# 1_MCU.net
KiCad netlist of a schematic drawn in Altium Designer
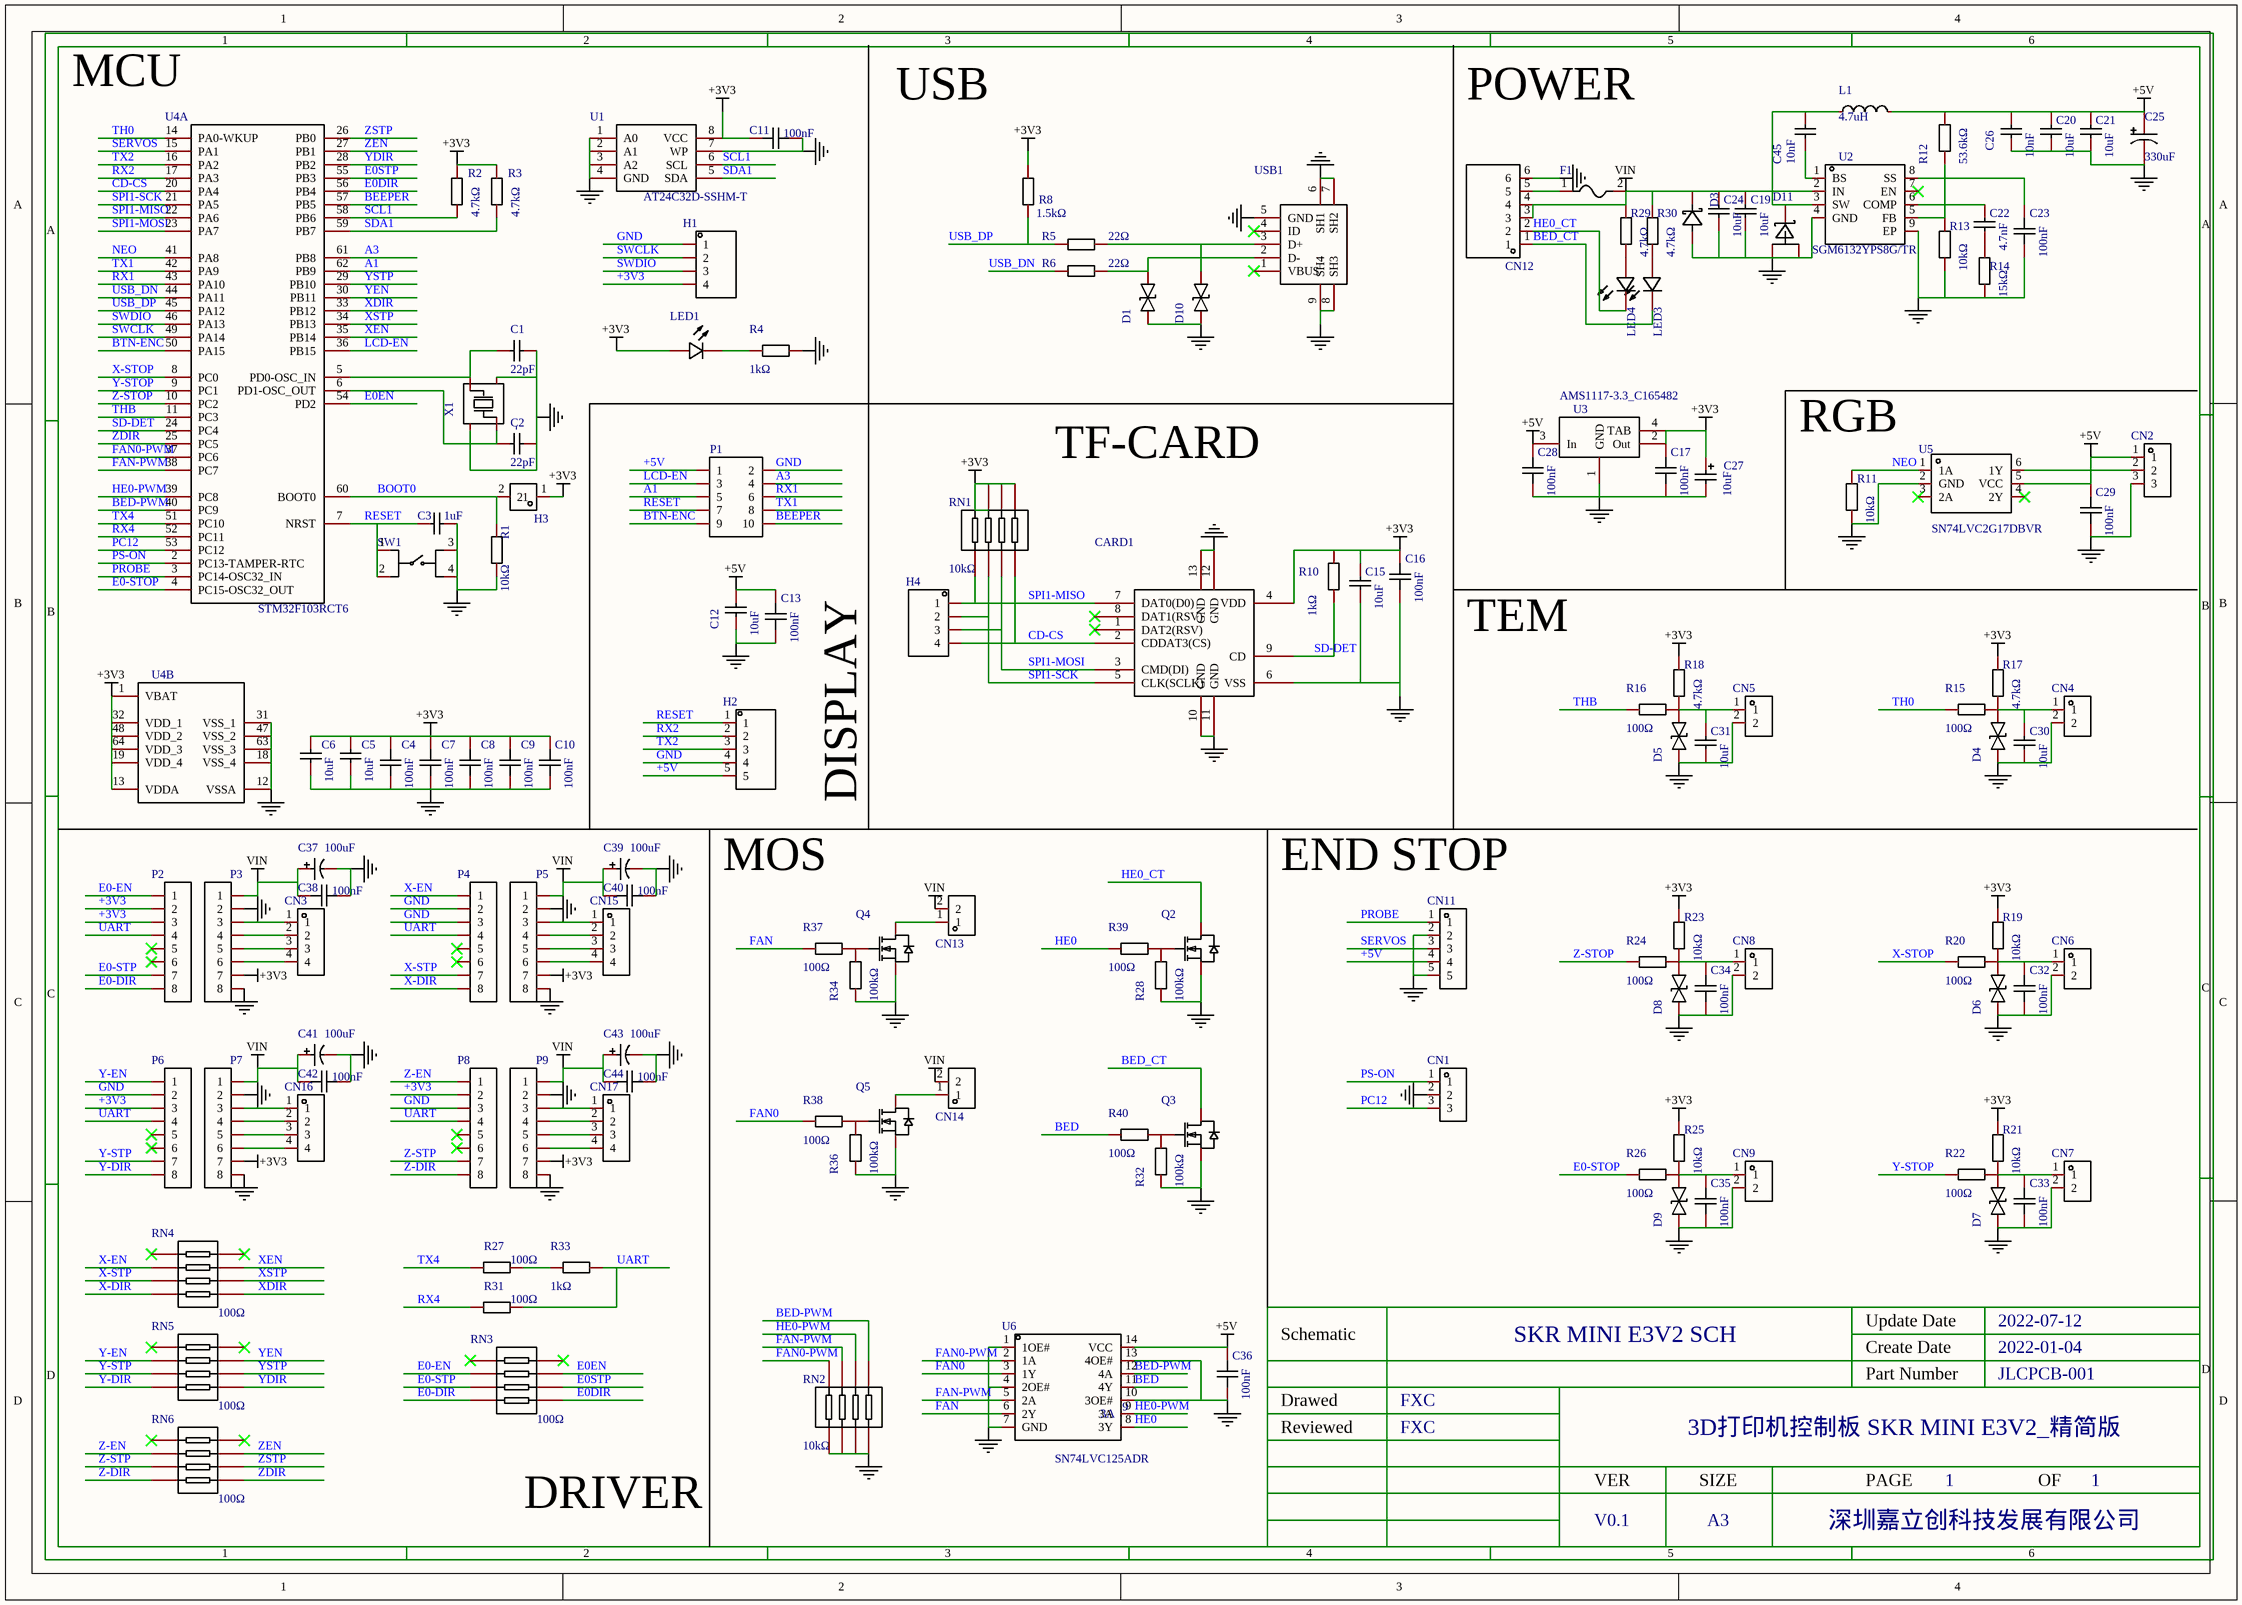
[diagram p0: 1_MCU.schdoc]

(export (version "E")
  (design (tool "Eeschema 10.0.6"))
  (components
    (comp (ref "C1")
      (value "22pF")
      (description "温度系数:NP0;电容体长:-;电容体宽:-;电容体厚度:-;精度:±5%;额定电压:50V;容值:22pF;")
      (fields
        (field (name "MANUFACTURER") "YAGEO(国巨)")
        (field (name "MANUFACTURER PART") "CC0603JRNPO9BN220")
      )
      (libsource (lib "altium-import") (part "root_0_CC0603JRNPO9BN220_"))
    )
    (comp (ref "C2")
      (value "22pF")
      (description "温度系数:NP0;电容体长:-;电容体宽:-;电容体厚度:-;精度:±5%;额定电压:50V;容值:22pF;")
      (fields
        (field (name "MANUFACTURER") "YAGEO(国巨)")
        (field (name "MANUFACTURER PART") "CC0603JRNPO9BN220")
      )
      (libsource (lib "altium-import") (part "root_0_CC0603JRNPO9BN220_"))
    )
    (comp (ref "C3")
      (value "1uF")
      (description "温度系数:X5R;额定电压:25V;电容体长:-;精度:±10%;电容体宽:-;电容体厚度:-;容值:1uF;")
      (fields
        (field (name "MANUFACTURER") "YAGEO(国巨)")
        (field (name "MANUFACTURER PART") "CC0603KRX5R8BB105")
      )
      (libsource (lib "altium-import") (part "root_0_CC0603KRX5R8BB105_"))
    )
    (comp (ref "C4")
      (value "100nF")
      (description "温度系数:X7R;容值:100nF;电容体长:-;精度:±10%;电容体宽:-;电容体厚度:-;额定电压:50V;")
      (fields
        (field (name "MANUFACTURER") "YAGEO(国巨)")
        (field (name "MANUFACTURER PART") "CC0603KRX7R9BB104")
      )
      (libsource (lib "altium-import") (part "root_1_CC0603KRX7R9BB104_"))
    )
    (comp (ref "C5")
      (value "10uF")
      (description "温度系数:X5R;精度:±10%;额定电压:16V;容值:10uF;")
      (fields (field (name "MANUFACTURER") "FH(风华)") (field (name "MANUFACTURER PART") "0603X106K160NT"))
      (libsource (lib "altium-import") (part "root_1_0603X106K160NT_"))
    )
    (comp (ref "C6")
      (value "10uF")
      (description "温度系数:X5R;精度:±10%;额定电压:16V;容值:10uF;")
      (fields (field (name "MANUFACTURER") "FH(风华)") (field (name "MANUFACTURER PART") "0603X106K160NT"))
      (libsource (lib "altium-import") (part "root_1_0603X106K160NT_"))
    )
    (comp (ref "C7")
      (value "100nF")
      (description "温度系数:X7R;容值:100nF;电容体长:-;精度:±10%;电容体宽:-;电容体厚度:-;额定电压:50V;")
      (fields
        (field (name "MANUFACTURER") "YAGEO(国巨)")
        (field (name "MANUFACTURER PART") "CC0603KRX7R9BB104")
      )
      (libsource (lib "altium-import") (part "root_1_CC0603KRX7R9BB104_"))
    )
    (comp (ref "C8")
      (value "100nF")
      (description "温度系数:X7R;容值:100nF;电容体长:-;精度:±10%;电容体宽:-;电容体厚度:-;额定电压:50V;")
      (fields
        (field (name "MANUFACTURER") "YAGEO(国巨)")
        (field (name "MANUFACTURER PART") "CC0603KRX7R9BB104")
      )
      (libsource (lib "altium-import") (part "root_1_CC0603KRX7R9BB104_"))
    )
    (comp (ref "C9")
      (value "100nF")
      (description "温度系数:X7R;容值:100nF;电容体长:-;精度:±10%;电容体宽:-;电容体厚度:-;额定电压:50V;")
      (fields
        (field (name "MANUFACTURER") "YAGEO(国巨)")
        (field (name "MANUFACTURER PART") "CC0603KRX7R9BB104")
      )
      (libsource (lib "altium-import") (part "root_1_CC0603KRX7R9BB104_"))
    )
    (comp (ref "C10")
      (value "100nF")
      (description "温度系数:X7R;容值:100nF;电容体长:-;精度:±10%;电容体宽:-;电容体厚度:-;额定电压:50V;")
      (fields
        (field (name "MANUFACTURER") "YAGEO(国巨)")
        (field (name "MANUFACTURER PART") "CC0603KRX7R9BB104")
      )
      (libsource (lib "altium-import") (part "root_1_CC0603KRX7R9BB104_"))
    )
    (comp (ref "C11")
      (value "100nF")
      (description "温度系数:X7R;容值:100nF;电容体长:-;精度:±10%;电容体宽:-;电容体厚度:-;额定电压:50V;")
      (fields
        (field (name "MANUFACTURER") "YAGEO(国巨)")
        (field (name "MANUFACTURER PART") "CC0603KRX7R9BB104")
      )
      (libsource (lib "altium-import") (part "root_2_CC0603KRX7R9BB104_"))
    )
    (comp (ref "C12")
      (value "10uF")
      (description "温度系数:X5R;精度:±10%;额定电压:16V;容值:10uF;")
      (fields (field (name "MANUFACTURER") "FH(风华)") (field (name "MANUFACTURER PART") "0603X106K160NT"))
      (libsource (lib "altium-import") (part "root_1_0603X106K160NT_"))
    )
    (comp (ref "C13")
      (value "100nF")
      (description "温度系数:X7R;容值:100nF;电容体长:-;精度:±10%;电容体宽:-;电容体厚度:-;额定电压:50V;")
      (fields
        (field (name "MANUFACTURER") "YAGEO(国巨)")
        (field (name "MANUFACTURER PART") "CC0603KRX7R9BB104")
      )
      (libsource (lib "altium-import") (part "root_1_CC0603KRX7R9BB104_"))
    )
    (comp (ref "C15")
      (value "10uF")
      (description "温度系数:X5R;精度:±10%;额定电压:16V;容值:10uF;")
      (fields (field (name "MANUFACTURER") "FH(风华)") (field (name "MANUFACTURER PART") "0603X106K160NT"))
      (libsource (lib "altium-import") (part "root_1_0603X106K160NT_"))
    )
    (comp (ref "C16")
      (value "100nF")
      (description "温度系数:X7R;容值:100nF;电容体长:-;精度:±10%;电容体宽:-;电容体厚度:-;额定电压:50V;")
      (fields
        (field (name "MANUFACTURER") "YAGEO(国巨)")
        (field (name "MANUFACTURER PART") "CC0603KRX7R9BB104")
      )
      (libsource (lib "altium-import") (part "root_1_CC0603KRX7R9BB104_"))
    )
    (comp (ref "C17")
      (value "100nF")
      (description "温度系数:X7R;容值:100nF;电容体长:-;精度:±10%;电容体宽:-;电容体厚度:-;额定电压:50V;")
      (fields
        (field (name "MANUFACTURER") "YAGEO(国巨)")
        (field (name "MANUFACTURER PART") "CC0603KRX7R9BB104")
      )
      (libsource (lib "altium-import") (part "root_1_CC0603KRX7R9BB104_"))
    )
    (comp (ref "C19")
      (value "10uF")
      (description "温度系数:X7R;精度:±10%;额定电压:50V;容值:10uF;")
      (fields
        (field (name "MANUFACTURER") "muRata(村田)")
        (field (name "MANUFACTURER PART") "GRM32ER71H106KA12L")
      )
      (libsource (lib "altium-import") (part "root_1_GRM32ER71H106KA12L_"))
    )
    (comp (ref "C20")
      (value "10uF")
      (description "温度系数:X7R;精度:±10%;额定电压:50V;容值:10uF;")
      (fields
        (field (name "MANUFACTURER") "muRata(村田)")
        (field (name "MANUFACTURER PART") "GRM32ER71H106KA12L")
      )
      (libsource (lib "altium-import") (part "root_1_GRM32ER71H106KA12L_"))
    )
    (comp (ref "C21")
      (value "10uF")
      (description "温度系数:X7R;精度:±10%;额定电压:50V;容值:10uF;")
      (fields
        (field (name "MANUFACTURER") "muRata(村田)")
        (field (name "MANUFACTURER PART") "GRM32ER71H106KA12L")
      )
      (libsource (lib "altium-import") (part "root_1_GRM32ER71H106KA12L_"))
    )
    (comp (ref "C22")
      (value "4.7nF")
      (description "温度系数:X7R;电容体长:-;精度:±10%;电容体宽:-;容值:4.7nF;电容体厚度:-;额定电压:50V;")
      (fields
        (field (name "MANUFACTURER") "YAGEO(国巨)")
        (field (name "MANUFACTURER PART") "CC0603KRX7R9BB472")
      )
      (libsource (lib "altium-import") (part "root_1_CC0603KRX7R9BB472_"))
    )
    (comp (ref "C23")
      (value "100nF")
      (description "温度系数:X7R;容值:100nF;电容体长:-;精度:±10%;电容体宽:-;电容体厚度:-;额定电压:50V;")
      (fields
        (field (name "MANUFACTURER") "YAGEO(国巨)")
        (field (name "MANUFACTURER PART") "CC0603KRX7R9BB104")
      )
      (libsource (lib "altium-import") (part "root_1_CC0603KRX7R9BB104_"))
    )
    (comp (ref "C24")
      (value "10uF")
      (description "温度系数:X7R;精度:±10%;额定电压:50V;容值:10uF;")
      (fields
        (field (name "MANUFACTURER") "muRata(村田)")
        (field (name "MANUFACTURER PART") "GRM32ER71H106KA12L")
      )
      (libsource (lib "altium-import") (part "root_1_GRM32ER71H106KA12L_"))
    )
    (comp (ref "C25")
      (value "330uF")
      (description "等效串联电阻:-;工作温度:-45℃~+105℃;纹波电流:-;工作寿命:2000hrs105℃;容值:330uF;电容体直径:8mm;精度:±20%;额定电压:25V;电容体长度:10mm;")
      (fields
        (field (name "MANUFACTURER") "lelon(台湾立隆)")
        (field (name "MANUFACTURER PART") "VEJ331M1ETR-0810")
      )
      (libsource (lib "altium-import") (part "root_0_VEJ331M1ETR-0810_"))
    )
    (comp (ref "C26")
      (value "10nF")
      (description "温度系数:X7R;电容体长:-;精度:±10%;电容体宽:-;电容体厚度:-;额定电压:50V;容值:10nF;")
      (fields
        (field (name "MANUFACTURER") "YAGEO(国巨)")
        (field (name "MANUFACTURER PART") "CC0603KRX7R9BB103")
      )
      (libsource (lib "altium-import") (part "root_1_CC0603KRX7R9BB103_"))
    )
    (comp (ref "C27")
      (value "10uF")
      (description "等效串联电阻:2.8Ω100kHz;工作温度:-55℃~+125℃;额定电压:16V;容值:10uF;精度:±10%;")
      (fields (field (name "MANUFACTURER") "AVX") (field (name "MANUFACTURER PART") "TAJB106K016RNJ"))
      (libsource (lib "altium-import") (part "root_3_TAJB106K016RNJ_"))
    )
    (comp (ref "C28")
      (value "100nF")
      (description "温度系数:X7R;容值:100nF;电容体长:-;精度:±10%;电容体宽:-;电容体厚度:-;额定电压:50V;")
      (fields
        (field (name "MANUFACTURER") "YAGEO(国巨)")
        (field (name "MANUFACTURER PART") "CC0603KRX7R9BB104")
      )
      (libsource (lib "altium-import") (part "root_1_CC0603KRX7R9BB104_"))
    )
    (comp (ref "C29")
      (value "100nF")
      (description "温度系数:X7R;容值:100nF;电容体长:-;精度:±10%;电容体宽:-;电容体厚度:-;额定电压:50V;")
      (fields
        (field (name "MANUFACTURER") "YAGEO(国巨)")
        (field (name "MANUFACTURER PART") "CC0603KRX7R9BB104")
      )
      (libsource (lib "altium-import") (part "root_1_CC0603KRX7R9BB104_"))
    )
    (comp (ref "C30")
      (value "10uF")
      (description "温度系数:X5R;精度:±10%;额定电压:16V;容值:10uF;")
      (fields (field (name "MANUFACTURER") "FH(风华)") (field (name "MANUFACTURER PART") "0603X106K160NT"))
      (libsource (lib "altium-import") (part "root_1_0603X106K160NT_"))
    )
    (comp (ref "C31")
      (value "10uF")
      (description "温度系数:X5R;精度:±10%;额定电压:16V;容值:10uF;")
      (fields (field (name "MANUFACTURER") "FH(风华)") (field (name "MANUFACTURER PART") "0603X106K160NT"))
      (libsource (lib "altium-import") (part "root_1_0603X106K160NT_"))
    )
    (comp (ref "C32")
      (value "100nF")
      (description "温度系数:X7R;容值:100nF;电容体长:-;精度:±10%;电容体宽:-;电容体厚度:-;额定电压:50V;")
      (fields
        (field (name "MANUFACTURER") "YAGEO(国巨)")
        (field (name "MANUFACTURER PART") "CC0603KRX7R9BB104")
      )
      (libsource (lib "altium-import") (part "root_1_CC0603KRX7R9BB104_"))
    )
    (comp (ref "C33")
      (value "100nF")
      (description "温度系数:X7R;容值:100nF;电容体长:-;精度:±10%;电容体宽:-;电容体厚度:-;额定电压:50V;")
      (fields
        (field (name "MANUFACTURER") "YAGEO(国巨)")
        (field (name "MANUFACTURER PART") "CC0603KRX7R9BB104")
      )
      (libsource (lib "altium-import") (part "root_1_CC0603KRX7R9BB104_"))
    )
    (comp (ref "C34")
      (value "100nF")
      (description "温度系数:X7R;容值:100nF;电容体长:-;精度:±10%;电容体宽:-;电容体厚度:-;额定电压:50V;")
      (fields
        (field (name "MANUFACTURER") "YAGEO(国巨)")
        (field (name "MANUFACTURER PART") "CC0603KRX7R9BB104")
      )
      (libsource (lib "altium-import") (part "root_1_CC0603KRX7R9BB104_"))
    )
    (comp (ref "C35")
      (value "100nF")
      (description "温度系数:X7R;容值:100nF;电容体长:-;精度:±10%;电容体宽:-;电容体厚度:-;额定电压:50V;")
      (fields
        (field (name "MANUFACTURER") "YAGEO(国巨)")
        (field (name "MANUFACTURER PART") "CC0603KRX7R9BB104")
      )
      (libsource (lib "altium-import") (part "root_1_CC0603KRX7R9BB104_"))
    )
    (comp (ref "C36")
      (value "100nF")
      (description "温度系数:X7R;容值:100nF;电容体长:-;精度:±10%;电容体宽:-;电容体厚度:-;额定电压:50V;")
      (fields
        (field (name "MANUFACTURER") "YAGEO(国巨)")
        (field (name "MANUFACTURER PART") "CC0603KRX7R9BB104")
      )
      (libsource (lib "altium-import") (part "root_1_CC0603KRX7R9BB104_"))
    )
    (comp (ref "C37")
      (value "100uF")
      (fields
        (field (name "MANUFACTURER") "CapXon(台湾丰宾)")
        (field (name "MANUFACTURER PART") "DV101M035E077ETR")
        (field (name "TOLERANCE") "±20%")
      )
      (libsource (lib "altium-import") (part "root_0_DV101M035E077ETR_"))
    )
    (comp (ref "C38")
      (value "100nF")
      (description "温度系数:X7R;容值:100nF;电容体长:-;精度:±10%;电容体宽:-;电容体厚度:-;额定电压:50V;")
      (fields
        (field (name "MANUFACTURER") "YAGEO(国巨)")
        (field (name "MANUFACTURER PART") "CC0603KRX7R9BB104")
      )
      (libsource (lib "altium-import") (part "root_2_CC0603KRX7R9BB104_"))
    )
    (comp (ref "C39")
      (value "100uF")
      (fields
        (field (name "MANUFACTURER") "CapXon(台湾丰宾)")
        (field (name "MANUFACTURER PART") "DV101M035E077ETR")
        (field (name "TOLERANCE") "±20%")
      )
      (libsource (lib "altium-import") (part "root_0_DV101M035E077ETR_"))
    )
    (comp (ref "C40")
      (value "100nF")
      (description "温度系数:X7R;容值:100nF;电容体长:-;精度:±10%;电容体宽:-;电容体厚度:-;额定电压:50V;")
      (fields
        (field (name "MANUFACTURER") "YAGEO(国巨)")
        (field (name "MANUFACTURER PART") "CC0603KRX7R9BB104")
      )
      (libsource (lib "altium-import") (part "root_2_CC0603KRX7R9BB104_"))
    )
    (comp (ref "C41")
      (value "100uF")
      (fields
        (field (name "MANUFACTURER") "CapXon(台湾丰宾)")
        (field (name "MANUFACTURER PART") "DV101M035E077ETR")
        (field (name "TOLERANCE") "±20%")
      )
      (libsource (lib "altium-import") (part "root_0_DV101M035E077ETR_"))
    )
    (comp (ref "C42")
      (value "100nF")
      (description "温度系数:X7R;容值:100nF;电容体长:-;精度:±10%;电容体宽:-;电容体厚度:-;额定电压:50V;")
      (fields
        (field (name "MANUFACTURER") "YAGEO(国巨)")
        (field (name "MANUFACTURER PART") "CC0603KRX7R9BB104")
      )
      (libsource (lib "altium-import") (part "root_2_CC0603KRX7R9BB104_"))
    )
    (comp (ref "C43")
      (value "100uF")
      (fields
        (field (name "MANUFACTURER") "CapXon(台湾丰宾)")
        (field (name "MANUFACTURER PART") "DV101M035E077ETR")
        (field (name "TOLERANCE") "±20%")
      )
      (libsource (lib "altium-import") (part "root_0_DV101M035E077ETR_"))
    )
    (comp (ref "C44")
      (value "100nF")
      (description "温度系数:X7R;容值:100nF;电容体长:-;精度:±10%;电容体宽:-;电容体厚度:-;额定电压:50V;")
      (fields
        (field (name "MANUFACTURER") "YAGEO(国巨)")
        (field (name "MANUFACTURER PART") "CC0603KRX7R9BB104")
      )
      (libsource (lib "altium-import") (part "root_2_CC0603KRX7R9BB104_"))
    )
    (comp (ref "C45")
      (value "10nF")
      (description "温度系数:X7R;电容体长:-;精度:±10%;电容体宽:-;电容体厚度:-;额定电压:50V;容值:10nF;")
      (fields
        (field (name "MANUFACTURER") "YAGEO(国巨)")
        (field (name "MANUFACTURER PART") "CC0603KRX7R9BB103")
      )
      (libsource (lib "altium-import") (part "root_1_CC0603KRX7R9BB103_"))
    )
    (comp (ref "CARD1")
      (value "TF-01A")
      (description "工作温度范围:-;本体最大高度:-;触头镀层:-;连接器类型:卡座;卡类型:MicroSD卡(TF卡);焊接温度(最大值):-;触头材质:-;卡连接方式:自弹式;")
      (fields (field (name "MANUFACTURER") "韩国韩荣"))
      (libsource (lib "altium-import") (part "root_0_TF-01A_"))
    )
    (comp (ref "CN1")
      (value "HX25003-3A")
      (description "系列:-;连接器类型:-;触头类型:-;间距:-;针脚数:-;")
      (fields (field (name "MANUFACTURER") "HX(红星)"))
      (libsource (lib "altium-import") (part "root_0_HX25003-3A_"))
    )
    (comp (ref "CN2")
      (value "HX25003-3A")
      (description "系列:-;连接器类型:-;触头类型:-;间距:-;针脚数:-;")
      (fields (field (name "MANUFACTURER") "HX(红星)"))
      (libsource (lib "altium-import") (part "root_0_HX25003-3A_"))
    )
    (comp (ref "CN3")
      (value "HX25003-4A")
      (description "系列:-;连接器类型:-;触头类型:-;间距:-;针脚数:-;")
      (fields (field (name "MANUFACTURER") "HX(红星)"))
      (libsource (lib "altium-import") (part "root_0_HX25003-4A_"))
    )
    (comp (ref "CN4")
      (value "HX25003-2A")
      (description "系列:-;连接器类型:-;触头类型:-;间距:-;针脚数:-;")
      (fields (field (name "MANUFACTURER") "HX(红星)"))
      (libsource (lib "altium-import") (part "root_0_HX25003-2A_"))
    )
    (comp (ref "CN5")
      (value "HX25003-2A")
      (description "系列:-;连接器类型:-;触头类型:-;间距:-;针脚数:-;")
      (fields (field (name "MANUFACTURER") "HX(红星)"))
      (libsource (lib "altium-import") (part "root_0_HX25003-2A_"))
    )
    (comp (ref "CN6")
      (value "HX25003-2A")
      (description "系列:-;连接器类型:-;触头类型:-;间距:-;针脚数:-;")
      (fields (field (name "MANUFACTURER") "HX(红星)"))
      (libsource (lib "altium-import") (part "root_0_HX25003-2A_"))
    )
    (comp (ref "CN7")
      (value "HX25003-2A")
      (description "系列:-;连接器类型:-;触头类型:-;间距:-;针脚数:-;")
      (fields (field (name "MANUFACTURER") "HX(红星)"))
      (libsource (lib "altium-import") (part "root_0_HX25003-2A_"))
    )
    (comp (ref "CN8")
      (value "HX25003-2A")
      (description "系列:-;连接器类型:-;触头类型:-;间距:-;针脚数:-;")
      (fields (field (name "MANUFACTURER") "HX(红星)"))
      (libsource (lib "altium-import") (part "root_0_HX25003-2A_"))
    )
    (comp (ref "CN9")
      (value "HX25003-2A")
      (description "系列:-;连接器类型:-;触头类型:-;间距:-;针脚数:-;")
      (fields (field (name "MANUFACTURER") "HX(红星)"))
      (libsource (lib "altium-import") (part "root_0_HX25003-2A_"))
    )
    (comp (ref "CN11")
      (value "HX25003-5A")
      (description "系列:-;连接器类型:-;触头类型:-;间距:-;针脚数:-;")
      (fields (field (name "MANUFACTURER") "HX(红星)"))
      (libsource (lib "altium-import") (part "root_0_HX25003-5A_"))
    )
    (comp (ref "CN12")
      (value "HB9500M-9.5-6P")
      (description "1、栅栏式接线端子2、间距9.5mm3、６PIN4、带盖子")
      (fields (field (name "MANUFACTURER") "KANGNEX(康奈克斯电气)"))
      (libsource (lib "altium-import") (part "root_2_HB9500M-9.5-6P_"))
    )
    (comp (ref "CN13")
      (value "HX25003-2A")
      (description "系列:-;连接器类型:-;触头类型:-;间距:-;针脚数:-;")
      (fields (field (name "MANUFACTURER") "HX(红星)"))
      (libsource (lib "altium-import") (part "root_2_mirrored_HX25003-2A_"))
    )
    (comp (ref "CN14")
      (value "HX25003-2A")
      (description "系列:-;连接器类型:-;触头类型:-;间距:-;针脚数:-;")
      (fields (field (name "MANUFACTURER") "HX(红星)"))
      (libsource (lib "altium-import") (part "root_2_mirrored_HX25003-2A_"))
    )
    (comp (ref "CN15")
      (value "HX25003-4A")
      (description "系列:-;连接器类型:-;触头类型:-;间距:-;针脚数:-;")
      (fields (field (name "MANUFACTURER") "HX(红星)"))
      (libsource (lib "altium-import") (part "root_0_HX25003-4A_"))
    )
    (comp (ref "CN16")
      (value "HX25003-4A")
      (description "系列:-;连接器类型:-;触头类型:-;间距:-;针脚数:-;")
      (fields (field (name "MANUFACTURER") "HX(红星)"))
      (libsource (lib "altium-import") (part "root_0_HX25003-4A_"))
    )
    (comp (ref "CN17")
      (value "HX25003-4A")
      (description "系列:-;连接器类型:-;触头类型:-;间距:-;针脚数:-;")
      (fields (field (name "MANUFACTURER") "HX(红星)"))
      (libsource (lib "altium-import") (part "root_0_HX25003-4A_"))
    )
    (comp (ref "D1")
      (value "0402ESDA-05N")
      (description "极性:Bidirectional;峰值脉冲电流（10/1000us）:-;箝位电压:50V;击穿电压（最小值）:-;反向关断电压（典型值）:5V;")
      (fields (field (name "MANUFACTURER") "BORN伯恩半导体"))
      (libsource (lib "altium-import") (part "root_1_0402ESDA-05N_"))
    )
    (comp (ref "D3")
      (value "SMCJ24A_C699044")
      (description "反向关断电压（典型值）:-;击穿电压（最小值）:-;箝位电压:-;峰值脉冲电流（10/1000us）:-;极性:-;")
      (fields (field (name "MANUFACTURER") "YANGJIE(扬杰)") (field (name "MANUFACTURER PART") "SMCJ24A"))
      (libsource (lib "altium-import") (part "root_3_SMCJ24A_C699044_"))
    )
    (comp (ref "D4")
      (value "0402ESDA-05N")
      (description "极性:Bidirectional;峰值脉冲电流（10/1000us）:-;箝位电压:50V;击穿电压（最小值）:-;反向关断电压（典型值）:5V;")
      (fields (field (name "MANUFACTURER") "BORN伯恩半导体"))
      (libsource (lib "altium-import") (part "root_1_0402ESDA-05N_"))
    )
    (comp (ref "D5")
      (value "0402ESDA-05N")
      (description "极性:Bidirectional;峰值脉冲电流（10/1000us）:-;箝位电压:50V;击穿电压（最小值）:-;反向关断电压（典型值）:5V;")
      (fields (field (name "MANUFACTURER") "BORN伯恩半导体"))
      (libsource (lib "altium-import") (part "root_1_0402ESDA-05N_"))
    )
    (comp (ref "D6")
      (value "0402ESDA-05N")
      (description "极性:Bidirectional;峰值脉冲电流（10/1000us）:-;箝位电压:50V;击穿电压（最小值）:-;反向关断电压（典型值）:5V;")
      (fields (field (name "MANUFACTURER") "BORN伯恩半导体"))
      (libsource (lib "altium-import") (part "root_1_0402ESDA-05N_"))
    )
    (comp (ref "D7")
      (value "0402ESDA-05N")
      (description "极性:Bidirectional;峰值脉冲电流（10/1000us）:-;箝位电压:50V;击穿电压（最小值）:-;反向关断电压（典型值）:5V;")
      (fields (field (name "MANUFACTURER") "BORN伯恩半导体"))
      (libsource (lib "altium-import") (part "root_1_0402ESDA-05N_"))
    )
    (comp (ref "D8")
      (value "0402ESDA-05N")
      (description "极性:Bidirectional;峰值脉冲电流（10/1000us）:-;箝位电压:50V;击穿电压（最小值）:-;反向关断电压（典型值）:5V;")
      (fields (field (name "MANUFACTURER") "BORN伯恩半导体"))
      (libsource (lib "altium-import") (part "root_1_0402ESDA-05N_"))
    )
    (comp (ref "D9")
      (value "0402ESDA-05N")
      (description "极性:Bidirectional;峰值脉冲电流（10/1000us）:-;箝位电压:50V;击穿电压（最小值）:-;反向关断电压（典型值）:5V;")
      (fields (field (name "MANUFACTURER") "BORN伯恩半导体"))
      (libsource (lib "altium-import") (part "root_1_0402ESDA-05N_"))
    )
    (comp (ref "D10")
      (value "0402ESDA-05N")
      (description "极性:Bidirectional;峰值脉冲电流（10/1000us）:-;箝位电压:50V;击穿电压（最小值）:-;反向关断电压（典型值）:5V;")
      (fields (field (name "MANUFACTURER") "BORN伯恩半导体"))
      (libsource (lib "altium-import") (part "root_1_0402ESDA-05N_"))
    )
    (comp (ref "D11")
      (value "SVM1045V")
      (description "直流反向耐压(Vr):45V;平均整流电流(Io):10A;正向压降(Vf):470mV@10A;")
      (fields (field (name "MANUFACTURER") "PANJIT(强茂)"))
      (libsource (lib "altium-import") (part "root_0_SVM1045V_"))
    )
    (comp (ref "F1")
      (value "JFC2410-1800TS")
      (description "产品:贴片式保险丝;保险丝类型:延时熔断/慢速熔断;额定电流:8A;标称冷电阻:7mΩ;标称电压降:-;分断能力:50A;熔断I²t:235.18;")
      (fields (field (name "MANUFACTURER") "JDTfuse集电通"))
      (libsource (lib "altium-import") (part "root_0_JFC2410-1800TS_"))
    )
    (comp (ref "H1")
      (value "B-2100S04P-A110")
      (description "额定电流:-;触头镀层:-;安装类型:直插;圆针/方针:-;额定电压:-;塑高:-;配合针长度:-;排数:1;总PIN位数:4;间距:2.54mm;触头材质:黄铜;行距:-;")
      (fields (field (name "MANUFACTURER") "Ckmtw(灿科盟)"))
      (libsource (lib "altium-import") (part "root_0_B-2100S04P-A110_"))
    )
    (comp (ref "H2")
      (value "B-2100S05P-A110")
      (description "额定电流:-;触头镀层:-;安装类型:直插;圆针/方针:-;额定电压:-;塑高:-;配合针长度:-;排数:1;总PIN位数:5;间距:2.54mm;触头材质:黄铜;行距:-;")
      (fields (field (name "MANUFACTURER") "Ckmtw(灿科盟)"))
      (libsource (lib "altium-import") (part "root_0_B-2100S05P-A110_"))
    )
    (comp (ref "H3")
      (value "PH-00218")
      (fields (field (name "MANUFACTURER") "Liansheng(连盛)"))
      (libsource (lib "altium-import") (part "root_2_PH-00218_"))
    )
    (comp (ref "H4")
      (value "B-2100S04P-A110")
      (description "额定电流:-;触头镀层:-;安装类型:直插;圆针/方针:-;额定电压:-;塑高:-;配合针长度:-;排数:1;总PIN位数:4;间距:2.54mm;触头材质:黄铜;行距:-;")
      (fields (field (name "MANUFACTURER") "Ckmtw(灿科盟)"))
      (libsource (lib "altium-import") (part "root_0_mirrored_B-2100S04P-A110_"))
    )
    (comp (ref "L1")
      (value "4.7uH")
      (description "精度:±20%;额定电流:-;直流电阻(DCR):-;电感值:10uH;")
      (fields
        (field (name "MANUFACTURER") "Sunltech(韩国顺磁)")
        (field (name "MANUFACTURER PART") "SLO0630H100MTT")
      )
      (libsource (lib "altium-import") (part "root_0_SLO0630H100MTT_"))
    )
    (comp (ref "LED1")
      (value "19-217/GHC-YR1S2/3T")
      (description "照明颜色:翠绿;色温-CCT（K）:-;主波长/色坐标:520~535nm;")
      (fields (field (name "MANUFACTURER") "EVERLIGHT(台湾亿光)"))
      (libsource (lib "altium-import") (part "root_0_19-217/GHC-YR1S2/3T_"))
    )
    (comp (ref "LED3")
      (value "19-213/R6W-BP2Q2B/3T")
      (description "照明颜色:红色;主波长/色坐标:-;")
      (fields (field (name "MANUFACTURER") "EVERLIGHT(台湾亿光)"))
      (libsource (lib "altium-import") (part "root_1_19-213/R6W-BP2Q2B/3T_"))
    )
    (comp (ref "LED4")
      (value "19-213/R6W-BP2Q2B/3T")
      (description "照明颜色:红色;主波长/色坐标:-;")
      (fields (field (name "MANUFACTURER") "EVERLIGHT(台湾亿光)"))
      (libsource (lib "altium-import") (part "root_1_19-213/R6W-BP2Q2B/3T_"))
    )
    (comp (ref "P1")
      (value "2.54-2*5P简牛")
      (description "连接器类型:简牛座;每排PIN数:5;排数:2;间距:2.54mm;行距:2.54mm;封装形式:直插;触头材质:-;触头镀层:-;")
      (fields (field (name "MANUFACTURER") "BOOMELE(博穆精密)"))
      (libsource (lib "altium-import") (part "root_0_2.54-2*5P简牛_"))
    )
    (comp (ref "P2")
      (value "2.54-1*8P母环保")
      (description "间距:2.54mm;行距:-;触头镀层:-;触头材质:-;安装类型:直插;塑高:-;总孔位数:8;排数:1;")
      (fields (field (name "MANUFACTURER") "BOOMELE(博穆精密)"))
      (libsource (lib "altium-import") (part "root_0_2.54-1*8P母环保_"))
    )
    (comp (ref "P3")
      (value "2.54-1*8P母环保")
      (description "间距:2.54mm;行距:-;触头镀层:-;触头材质:-;安装类型:直插;塑高:-;总孔位数:8;排数:1;")
      (fields (field (name "MANUFACTURER") "BOOMELE(博穆精密)"))
      (libsource (lib "altium-import") (part "root_0_mirrored_2.54-1*8P母环保_"))
    )
    (comp (ref "P4")
      (value "2.54-1*8P母环保")
      (description "间距:2.54mm;行距:-;触头镀层:-;触头材质:-;安装类型:直插;塑高:-;总孔位数:8;排数:1;")
      (fields (field (name "MANUFACTURER") "BOOMELE(博穆精密)"))
      (libsource (lib "altium-import") (part "root_0_2.54-1*8P母环保_"))
    )
    (comp (ref "P5")
      (value "2.54-1*8P母环保")
      (description "间距:2.54mm;行距:-;触头镀层:-;触头材质:-;安装类型:直插;塑高:-;总孔位数:8;排数:1;")
      (fields (field (name "MANUFACTURER") "BOOMELE(博穆精密)"))
      (libsource (lib "altium-import") (part "root_0_mirrored_2.54-1*8P母环保_"))
    )
    (comp (ref "P6")
      (value "2.54-1*8P母环保")
      (description "间距:2.54mm;行距:-;触头镀层:-;触头材质:-;安装类型:直插;塑高:-;总孔位数:8;排数:1;")
      (fields (field (name "MANUFACTURER") "BOOMELE(博穆精密)"))
      (libsource (lib "altium-import") (part "root_0_2.54-1*8P母环保_"))
    )
    (comp (ref "P7")
      (value "2.54-1*8P母环保")
      (description "间距:2.54mm;行距:-;触头镀层:-;触头材质:-;安装类型:直插;塑高:-;总孔位数:8;排数:1;")
      (fields (field (name "MANUFACTURER") "BOOMELE(博穆精密)"))
      (libsource (lib "altium-import") (part "root_0_mirrored_2.54-1*8P母环保_"))
    )
    (comp (ref "P8")
      (value "2.54-1*8P母环保")
      (description "间距:2.54mm;行距:-;触头镀层:-;触头材质:-;安装类型:直插;塑高:-;总孔位数:8;排数:1;")
      (fields (field (name "MANUFACTURER") "BOOMELE(博穆精密)"))
      (libsource (lib "altium-import") (part "root_0_2.54-1*8P母环保_"))
    )
    (comp (ref "P9")
      (value "2.54-1*8P母环保")
      (description "间距:2.54mm;行距:-;触头镀层:-;触头材质:-;安装类型:直插;塑高:-;总孔位数:8;排数:1;")
      (fields (field (name "MANUFACTURER") "BOOMELE(博穆精密)"))
      (libsource (lib "altium-import") (part "root_0_mirrored_2.54-1*8P母环保_"))
    )
    (comp (ref "Q2")
      (value "NCE6050KA")
      (fields (field (name "MANUFACTURER") "无锡新洁能"))
      (libsource (lib "altium-import") (part "root_0_NCE6050KA_"))
    )
    (comp (ref "Q3")
      (value "NCE6050KA")
      (fields (field (name "MANUFACTURER") "无锡新洁能"))
      (libsource (lib "altium-import") (part "root_0_NCE6050KA_"))
    )
    (comp (ref "Q4")
      (value "AO3400A_C20917")
      (fields (field (name "MANUFACTURER") "AOS") (field (name "MANUFACTURER PART") "AO3400A"))
      (libsource (lib "altium-import") (part "root_0_AO3400A_C20917_"))
    )
    (comp (ref "Q5")
      (value "AO3400A_C20917")
      (fields (field (name "MANUFACTURER") "AOS") (field (name "MANUFACTURER PART") "AO3400A"))
      (libsource (lib "altium-import") (part "root_0_AO3400A_C20917_"))
    )
    (comp (ref "R1")
      (value "10kΩ")
      (description "精度:±1%;温度系数:±100ppm/℃;阻值:10kΩ;功率:100mW;最大工作电压:75V;工作温度范围:-55℃~+155℃;")
      (fields (field (name "MANUFACTURER") "YAGEO(国巨)") (field (name "MANUFACTURER PART") "RC0603FR-0710KL"))
      (libsource (lib "altium-import") (part "root_3_RC0603FR-0710KL_"))
    )
    (comp (ref "R2")
      (value "4.7kΩ")
      (description "精度:±1%;阻值:4.7kΩ;温度系数:±100ppm/℃;功率:100mW;最大工作电压:75V;工作温度范围:-55℃~+155℃;")
      (fields (field (name "MANUFACTURER") "YAGEO(国巨)") (field (name "MANUFACTURER PART") "RC0603FR-074K7L"))
      (libsource (lib "altium-import") (part "root_1_RC0603FR-074K7L_"))
    )
    (comp (ref "R3")
      (value "4.7kΩ")
      (description "精度:±1%;阻值:4.7kΩ;温度系数:±100ppm/℃;功率:100mW;最大工作电压:75V;工作温度范围:-55℃~+155℃;")
      (fields (field (name "MANUFACTURER") "YAGEO(国巨)") (field (name "MANUFACTURER PART") "RC0603FR-074K7L"))
      (libsource (lib "altium-import") (part "root_1_RC0603FR-074K7L_"))
    )
    (comp (ref "R4")
      (value "1kΩ")
      (description "精度:±1%;温度系数:±100ppm/℃;阻值:1kΩ;功率:100mW;最大工作电压:75V;工作温度范围:-55℃~+155℃;")
      (fields (field (name "MANUFACTURER") "YAGEO(国巨)") (field (name "MANUFACTURER PART") "RC0603FR-071KL"))
      (libsource (lib "altium-import") (part "root_0_RC0603FR-071KL_"))
    )
    (comp (ref "R5")
      (value "22Ω")
      (fields
        (field (name "MANUFACTURER") "YAGEO(国巨)")
        (field (name "MANUFACTURER PART") "RC0603FR-0722RL")
        (field (name "TOLERANCE") "±1%")
      )
      (libsource (lib "altium-import") (part "root_0_RC0603FR-0722RL_"))
    )
    (comp (ref "R6")
      (value "22Ω")
      (fields
        (field (name "MANUFACTURER") "YAGEO(国巨)")
        (field (name "MANUFACTURER PART") "RC0603FR-0722RL")
        (field (name "TOLERANCE") "±1%")
      )
      (libsource (lib "altium-import") (part "root_0_RC0603FR-0722RL_"))
    )
    (comp (ref "R8")
      (value "1.5kΩ")
      (description "阻值:1.5kΩ;精度:±1%;温度系数:±100ppm/℃;功率:1/10W;最大工作电压:75V;工作温度范围:-55℃~+155℃;")
      (fields
        (field (name "MANUFACTURER") "UNI-ROYAL(厚声)")
        (field (name "MANUFACTURER PART") "0603WAF1501T5E")
      )
      (libsource (lib "altium-import") (part "root_1_0603WAF1501T5E_"))
    )
    (comp (ref "R10")
      (value "1kΩ")
      (description "精度:±1%;温度系数:±100ppm/℃;阻值:1kΩ;功率:100mW;最大工作电压:75V;工作温度范围:-55℃~+155℃;")
      (fields (field (name "MANUFACTURER") "YAGEO(国巨)") (field (name "MANUFACTURER PART") "RC0603FR-071KL"))
      (libsource (lib "altium-import") (part "root_1_RC0603FR-071KL_"))
    )
    (comp (ref "R11")
      (value "10kΩ")
      (description "精度:±1%;温度系数:±100ppm/℃;阻值:10kΩ;功率:100mW;最大工作电压:75V;工作温度范围:-55℃~+155℃;")
      (fields (field (name "MANUFACTURER") "YAGEO(国巨)") (field (name "MANUFACTURER PART") "RC0603FR-0710KL"))
      (libsource (lib "altium-import") (part "root_1_RC0603FR-0710KL_"))
    )
    (comp (ref "R12")
      (value "53.6kΩ")
      (description "精度:±1%;功率:1/10W;电阻类型:厚膜电阻;最大工作电压:75V;温度系数:±100ppm/℃;工作温度范围:-55℃~+155℃;阻值:53.6kΩ;")
      (fields
        (field (name "MANUFACTURER") "UNI-ROYAL(厚声)")
        (field (name "MANUFACTURER PART") "0603WAF5362T5E")
      )
      (libsource (lib "altium-import") (part "root_1_0603WAF5362T5E_"))
    )
    (comp (ref "R13")
      (value "10kΩ")
      (description "精度:±1%;温度系数:±100ppm/℃;阻值:10kΩ;功率:100mW;最大工作电压:75V;工作温度范围:-55℃~+155℃;")
      (fields (field (name "MANUFACTURER") "YAGEO(国巨)") (field (name "MANUFACTURER PART") "RC0603FR-0710KL"))
      (libsource (lib "altium-import") (part "root_1_RC0603FR-0710KL_"))
    )
    (comp (ref "R14")
      (value "15kΩ")
      (fields
        (field (name "MANUFACTURER") "YAGEO(国巨)")
        (field (name "MANUFACTURER PART") "AC0603FR-0715KL")
        (field (name "TOLERANCE") "±1%")
      )
      (libsource (lib "altium-import") (part "root_1_AC0603FR-0715KL_"))
    )
    (comp (ref "R15")
      (value "100Ω")
      (fields
        (field (name "MANUFACTURER") "YAGEO(国巨)")
        (field (name "MANUFACTURER PART") "RC0603FR-07100RL")
        (field (name "TOLERANCE") "±1%")
      )
      (libsource (lib "altium-import") (part "root_0_RC0603FR-07100RL_"))
    )
    (comp (ref "R16")
      (value "100Ω")
      (fields
        (field (name "MANUFACTURER") "YAGEO(国巨)")
        (field (name "MANUFACTURER PART") "RC0603FR-07100RL")
        (field (name "TOLERANCE") "±1%")
      )
      (libsource (lib "altium-import") (part "root_0_RC0603FR-07100RL_"))
    )
    (comp (ref "R17")
      (value "4.7kΩ")
      (description "精度:±1%;阻值:4.7kΩ;温度系数:±100ppm/℃;功率:100mW;最大工作电压:75V;工作温度范围:-55℃~+155℃;")
      (fields (field (name "MANUFACTURER") "YAGEO(国巨)") (field (name "MANUFACTURER PART") "RC0603FR-074K7L"))
      (libsource (lib "altium-import") (part "root_1_RC0603FR-074K7L_"))
    )
    (comp (ref "R18")
      (value "4.7kΩ")
      (description "精度:±1%;阻值:4.7kΩ;温度系数:±100ppm/℃;功率:100mW;最大工作电压:75V;工作温度范围:-55℃~+155℃;")
      (fields (field (name "MANUFACTURER") "YAGEO(国巨)") (field (name "MANUFACTURER PART") "RC0603FR-074K7L"))
      (libsource (lib "altium-import") (part "root_1_RC0603FR-074K7L_"))
    )
    (comp (ref "R19")
      (value "10kΩ")
      (description "精度:±1%;温度系数:±100ppm/℃;阻值:10kΩ;功率:100mW;最大工作电压:75V;工作温度范围:-55℃~+155℃;")
      (fields (field (name "MANUFACTURER") "YAGEO(国巨)") (field (name "MANUFACTURER PART") "RC0603FR-0710KL"))
      (libsource (lib "altium-import") (part "root_1_RC0603FR-0710KL_"))
    )
    (comp (ref "R20")
      (value "100Ω")
      (fields
        (field (name "MANUFACTURER") "YAGEO(国巨)")
        (field (name "MANUFACTURER PART") "RC0603FR-07100RL")
        (field (name "TOLERANCE") "±1%")
      )
      (libsource (lib "altium-import") (part "root_0_RC0603FR-07100RL_"))
    )
    (comp (ref "R21")
      (value "10kΩ")
      (description "精度:±1%;温度系数:±100ppm/℃;阻值:10kΩ;功率:100mW;最大工作电压:75V;工作温度范围:-55℃~+155℃;")
      (fields (field (name "MANUFACTURER") "YAGEO(国巨)") (field (name "MANUFACTURER PART") "RC0603FR-0710KL"))
      (libsource (lib "altium-import") (part "root_1_RC0603FR-0710KL_"))
    )
    (comp (ref "R22")
      (value "100Ω")
      (fields
        (field (name "MANUFACTURER") "YAGEO(国巨)")
        (field (name "MANUFACTURER PART") "RC0603FR-07100RL")
        (field (name "TOLERANCE") "±1%")
      )
      (libsource (lib "altium-import") (part "root_0_RC0603FR-07100RL_"))
    )
    (comp (ref "R23")
      (value "10kΩ")
      (description "精度:±1%;温度系数:±100ppm/℃;阻值:10kΩ;功率:100mW;最大工作电压:75V;工作温度范围:-55℃~+155℃;")
      (fields (field (name "MANUFACTURER") "YAGEO(国巨)") (field (name "MANUFACTURER PART") "RC0603FR-0710KL"))
      (libsource (lib "altium-import") (part "root_1_RC0603FR-0710KL_"))
    )
    (comp (ref "R24")
      (value "100Ω")
      (fields
        (field (name "MANUFACTURER") "YAGEO(国巨)")
        (field (name "MANUFACTURER PART") "RC0603FR-07100RL")
        (field (name "TOLERANCE") "±1%")
      )
      (libsource (lib "altium-import") (part "root_0_RC0603FR-07100RL_"))
    )
    (comp (ref "R25")
      (value "10kΩ")
      (description "精度:±1%;温度系数:±100ppm/℃;阻值:10kΩ;功率:100mW;最大工作电压:75V;工作温度范围:-55℃~+155℃;")
      (fields (field (name "MANUFACTURER") "YAGEO(国巨)") (field (name "MANUFACTURER PART") "RC0603FR-0710KL"))
      (libsource (lib "altium-import") (part "root_1_RC0603FR-0710KL_"))
    )
    (comp (ref "R26")
      (value "100Ω")
      (fields
        (field (name "MANUFACTURER") "YAGEO(国巨)")
        (field (name "MANUFACTURER PART") "RC0603FR-07100RL")
        (field (name "TOLERANCE") "±1%")
      )
      (libsource (lib "altium-import") (part "root_0_RC0603FR-07100RL_"))
    )
    (comp (ref "R27")
      (value "100Ω")
      (fields
        (field (name "MANUFACTURER") "YAGEO(国巨)")
        (field (name "MANUFACTURER PART") "RC0603FR-07100RL")
        (field (name "TOLERANCE") "±1%")
      )
      (libsource (lib "altium-import") (part "root_0_RC0603FR-07100RL_"))
    )
    (comp (ref "R28")
      (value "100kΩ")
      (description "精度:±1%;阻值:100kΩ;温度系数:±100ppm/℃;功率:100mW;最大工作电压:75V;工作温度范围:-55℃~+155℃;")
      (fields (field (name "MANUFACTURER") "YAGEO(国巨)") (field (name "MANUFACTURER PART") "RC0603FR-07100KL"))
      (libsource (lib "altium-import") (part "root_1_RC0603FR-07100KL_"))
    )
    (comp (ref "R29")
      (value "4.7kΩ")
      (description "精度:±1%;阻值:4.7kΩ;温度系数:±100ppm/℃;功率:100mW;最大工作电压:75V;工作温度范围:-55℃~+155℃;")
      (fields (field (name "MANUFACTURER") "YAGEO(国巨)") (field (name "MANUFACTURER PART") "RC0603FR-074K7L"))
      (libsource (lib "altium-import") (part "root_1_RC0603FR-074K7L_"))
    )
    (comp (ref "R30")
      (value "4.7kΩ")
      (description "精度:±1%;阻值:4.7kΩ;温度系数:±100ppm/℃;功率:100mW;最大工作电压:75V;工作温度范围:-55℃~+155℃;")
      (fields (field (name "MANUFACTURER") "YAGEO(国巨)") (field (name "MANUFACTURER PART") "RC0603FR-074K7L"))
      (libsource (lib "altium-import") (part "root_1_RC0603FR-074K7L_"))
    )
    (comp (ref "R31")
      (value "100Ω")
      (fields
        (field (name "MANUFACTURER") "YAGEO(国巨)")
        (field (name "MANUFACTURER PART") "RC0603FR-07100RL")
        (field (name "TOLERANCE") "±1%")
      )
      (libsource (lib "altium-import") (part "root_0_RC0603FR-07100RL_"))
    )
    (comp (ref "R32")
      (value "100kΩ")
      (description "精度:±1%;阻值:100kΩ;温度系数:±100ppm/℃;功率:100mW;最大工作电压:75V;工作温度范围:-55℃~+155℃;")
      (fields (field (name "MANUFACTURER") "YAGEO(国巨)") (field (name "MANUFACTURER PART") "RC0603FR-07100KL"))
      (libsource (lib "altium-import") (part "root_1_RC0603FR-07100KL_"))
    )
    (comp (ref "R33")
      (value "1kΩ")
      (description "精度:±1%;温度系数:±100ppm/℃;阻值:1kΩ;功率:100mW;最大工作电压:75V;工作温度范围:-55℃~+155℃;")
      (fields (field (name "MANUFACTURER") "YAGEO(国巨)") (field (name "MANUFACTURER PART") "RC0603FR-071KL"))
      (libsource (lib "altium-import") (part "root_0_RC0603FR-071KL_"))
    )
    (comp (ref "R34")
      (value "100kΩ")
      (description "精度:±1%;阻值:100kΩ;温度系数:±100ppm/℃;功率:100mW;最大工作电压:75V;工作温度范围:-55℃~+155℃;")
      (fields (field (name "MANUFACTURER") "YAGEO(国巨)") (field (name "MANUFACTURER PART") "RC0603FR-07100KL"))
      (libsource (lib "altium-import") (part "root_1_RC0603FR-07100KL_"))
    )
    (comp (ref "R36")
      (value "100kΩ")
      (description "精度:±1%;阻值:100kΩ;温度系数:±100ppm/℃;功率:100mW;最大工作电压:75V;工作温度范围:-55℃~+155℃;")
      (fields (field (name "MANUFACTURER") "YAGEO(国巨)") (field (name "MANUFACTURER PART") "RC0603FR-07100KL"))
      (libsource (lib "altium-import") (part "root_1_RC0603FR-07100KL_"))
    )
    (comp (ref "R37")
      (value "100Ω")
      (fields
        (field (name "MANUFACTURER") "YAGEO(国巨)")
        (field (name "MANUFACTURER PART") "RC0603FR-07100RL")
        (field (name "TOLERANCE") "±1%")
      )
      (libsource (lib "altium-import") (part "root_0_RC0603FR-07100RL_"))
    )
    (comp (ref "R38")
      (value "100Ω")
      (fields
        (field (name "MANUFACTURER") "YAGEO(国巨)")
        (field (name "MANUFACTURER PART") "RC0603FR-07100RL")
        (field (name "TOLERANCE") "±1%")
      )
      (libsource (lib "altium-import") (part "root_0_RC0603FR-07100RL_"))
    )
    (comp (ref "R39")
      (value "100Ω")
      (fields
        (field (name "MANUFACTURER") "YAGEO(国巨)")
        (field (name "MANUFACTURER PART") "RC0603FR-07100RL")
        (field (name "TOLERANCE") "±1%")
      )
      (libsource (lib "altium-import") (part "root_0_RC0603FR-07100RL_"))
    )
    (comp (ref "R40")
      (value "100Ω")
      (fields
        (field (name "MANUFACTURER") "YAGEO(国巨)")
        (field (name "MANUFACTURER PART") "RC0603FR-07100RL")
        (field (name "TOLERANCE") "±1%")
      )
      (libsource (lib "altium-import") (part "root_0_RC0603FR-07100RL_"))
    )
    (comp (ref "RN1")
      (value "10kΩ")
      (description "阻值:10kΩ;精度:±5%;单个元件功率:62.5mW;温度系数:±200ppm/℃;电阻器数:4;引脚数:8;")
      (fields (field (name "MANUFACTURER") "YAGEO(国巨)") (field (name "MANUFACTURER PART") "YC164-JR-0710KL"))
      (libsource (lib "altium-import") (part "root_0_YC164-JR-0710KL_"))
    )
    (comp (ref "RN2")
      (value "10kΩ")
      (description "阻值:10kΩ;精度:±5%;单个元件功率:62.5mW;温度系数:±200ppm/℃;电阻器数:4;引脚数:8;")
      (fields (field (name "MANUFACTURER") "YAGEO(国巨)") (field (name "MANUFACTURER PART") "YC164-JR-0710KL"))
      (libsource (lib "altium-import") (part "root_0_YC164-JR-0710KL_"))
    )
    (comp (ref "RN3")
      (value "100Ω")
      (description "电阻器数:4;精度:±5%;引脚数:8;电阻长:-;电阻宽:-;阻值:100Ω;单个元件功率:1/16W;电阻高:-;温度系数:±200ppm/℃;")
      (fields
        (field (name "MANUFACTURER") "UNI-ROYAL(厚声)")
        (field (name "MANUFACTURER PART") "4D03WGJ0101T5E")
      )
      (libsource (lib "altium-import") (part "root_0_4D03WGJ0101T5E_"))
    )
    (comp (ref "RN4")
      (value "100Ω")
      (description "电阻器数:4;精度:±5%;引脚数:8;电阻长:-;电阻宽:-;阻值:100Ω;单个元件功率:1/16W;电阻高:-;温度系数:±200ppm/℃;")
      (fields
        (field (name "MANUFACTURER") "UNI-ROYAL(厚声)")
        (field (name "MANUFACTURER PART") "4D03WGJ0101T5E")
      )
      (libsource (lib "altium-import") (part "root_0_4D03WGJ0101T5E_"))
    )
    (comp (ref "RN5")
      (value "100Ω")
      (description "电阻器数:4;精度:±5%;引脚数:8;电阻长:-;电阻宽:-;阻值:100Ω;单个元件功率:1/16W;电阻高:-;温度系数:±200ppm/℃;")
      (fields
        (field (name "MANUFACTURER") "UNI-ROYAL(厚声)")
        (field (name "MANUFACTURER PART") "4D03WGJ0101T5E")
      )
      (libsource (lib "altium-import") (part "root_0_4D03WGJ0101T5E_"))
    )
    (comp (ref "RN6")
      (value "100Ω")
      (description "电阻器数:4;精度:±5%;引脚数:8;电阻长:-;电阻宽:-;阻值:100Ω;单个元件功率:1/16W;电阻高:-;温度系数:±200ppm/℃;")
      (fields
        (field (name "MANUFACTURER") "UNI-ROYAL(厚声)")
        (field (name "MANUFACTURER PART") "4D03WGJ0101T5E")
      )
      (libsource (lib "altium-import") (part "root_0_4D03WGJ0101T5E_"))
    )
    (comp (ref "SW1")
      (value "K2-6639SP-C4SC-04")
      (fields (field (name "MANUFACTURER") "韩国韩荣"))
      (libsource (lib "altium-import") (part "root_0_K2-6639SP-C4SC-04_"))
    )
    (comp (ref "U1")
      (value "AT24C32D-SSHM-T")
      (description "存储器接口类型:I2C;存储器容量:32Kb(4Kx8);工作电压:1.7V~5.5V;")
      (fields (field (name "SYMBOL") "AT24C32D-SSHM-T") (field (name "MANUFACTURER") "MICROCHIP(美国微芯)"))
      (libsource (lib "altium-import") (part "root_0_AT24C32D-SSHM-T_"))
    )
    (comp (ref "U2")
      (value "SGM6132YPS8G/TR")
      (description "可输出电流:3A;最大输入电压:28.5V;")
      (fields (field (name "SYMBOL") "SGM6132YPS8G/TR") (field (name "MANUFACTURER") "SGMICRO(圣邦微)"))
      (libsource (lib "altium-import") (part "root_0_SGM6132YPS8G/TR_"))
    )
    (comp (ref "U3")
      (value "SK1117-3.3")
      (description "输出类型:-;最大输入电压:-;输出电压(固定):-;输出电压(可调):-;压降(max):-;静态电流(Iq):-;")
      (fields (field (name "SYMBOL") "AMS1117-3.3_C165482") (field (name "MANUFACTURER") "SHIKUES(时科)"))
      (libsource (lib "altium-import") (part "root_0_SK1117-3.3_"))
    )
    (comp (ref "U4")
      (value "STM32F103RCT6")
      (description "工作电压:2V~3.6V;主频（MAX):72MHz;")
      (fields (field (name "SYMBOL") "STM32F103RCT6") (field (name "MANUFACTURER") "ST(意法半导体)"))
      (libsource (lib "altium-import") (part "root_0_STM32F103RCT6_"))
    )
    (comp (ref "U5")
      (value "SN74LVC2G17DBVR")
      (description "逻辑电路的归属系列:74LVC;逻辑类型:缓冲器，非反向;元件数:2;每元件位数:1;")
      (fields (field (name "SYMBOL") "SN74LVC2G17DBVR") (field (name "MANUFACTURER") "TI(德州仪器)"))
      (libsource (lib "altium-import") (part "root_0_SN74LVC2G17DBVR_"))
    )
    (comp (ref "U6")
      (value "SN74LVC125ADR")
      (description "逻辑电路的归属系列:74LVC;逻辑类型:缓冲器，非反向;元件数:4;每元件位数:1;")
      (fields
        (field (name "SYMBOL") "SN74LVC125ADR")
        (field (name "MANUFACTURER") "TI(德州仪器)")
        (field (name "NAME") "3A")
        (field (name "NUMBER") "9")
      )
      (libsource (lib "altium-import") (part "root_0_SN74LVC125ADR_"))
    )
    (comp (ref "USB1")
      (value "MicroXNJ")
      (description "连接器类型:Micro-B;标准:USB2.0;公母:母座;触点数量:5;端口数量:1;安装方式:卧贴;额定电流-电源:1A;工作温度范围:-20℃~+85℃;")
      (fields (field (name "MANUFACTURER") "SHOUHAN(首韩)"))
      (libsource (lib "altium-import") (part "root_0_MicroXNJ_"))
    )
    (comp (ref "X1")
      (value "-")
      (description "频率公差:-;负载电容:-;工作温度:-;晶振类型:-;等效串联电阻(ESR):-;频率:-;频率稳定度:-;")
      (fields (field (name "MANUFACTURER") "TAE(雅晶鑫)") (field (name "MANUFACTURER PART") "TAXM8M4RDBCCT2T"))
      (libsource (lib "altium-import") (part "root_1_TAXM8M4RDBCCT2T_"))
    )
  )
  (nets
    (net (code "1") (name "+3V3") (class "Default")
      (node (ref "C10") (pin "2") (pinfunction "2_2") (pintype "passive"))
      (node (ref "C11") (pin "2") (pinfunction "2_2") (pintype "passive"))
      (node (ref "C15") (pin "2") (pinfunction "2_2") (pintype "passive"))
      (node (ref "C16") (pin "2") (pinfunction "2_2") (pintype "passive"))
      (node (ref "C17") (pin "2") (pinfunction "2_2") (pintype "passive"))
      (node (ref "C27") (pin "1") (pinfunction "1_1") (pintype "passive"))
      (node (ref "C4") (pin "2") (pinfunction "2_2") (pintype "passive"))
      (node (ref "C5") (pin "2") (pinfunction "2_2") (pintype "passive"))
      (node (ref "C6") (pin "2") (pinfunction "2_2") (pintype "passive"))
      (node (ref "C7") (pin "2") (pinfunction "2_2") (pintype "passive"))
      (node (ref "C8") (pin "2") (pinfunction "2_2") (pintype "passive"))
      (node (ref "C9") (pin "2") (pinfunction "2_2") (pintype "passive"))
      (node (ref "CARD1") (pin "4") (pinfunction "VDD_4") (pintype "passive"))
      (node (ref "H1") (pin "4") (pinfunction "4_4") (pintype "passive"))
      (node (ref "H3") (pin "1") (pinfunction "1_1") (pintype "passive"))
      (node (ref "LED1") (pin "1") (pinfunction "A_1") (pintype "passive"))
      (node (ref "P2") (pin "2") (pinfunction "2_2") (pintype "passive"))
      (node (ref "P2") (pin "3") (pinfunction "3_3") (pintype "passive"))
      (node (ref "P3") (pin "7") (pinfunction "7_7") (pintype "passive"))
      (node (ref "P5") (pin "7") (pinfunction "7_7") (pintype "passive"))
      (node (ref "P6") (pin "3") (pinfunction "3_3") (pintype "passive"))
      (node (ref "P7") (pin "7") (pinfunction "7_7") (pintype "passive"))
      (node (ref "P8") (pin "2") (pinfunction "2_2") (pintype "passive"))
      (node (ref "P9") (pin "7") (pinfunction "7_7") (pintype "passive"))
      (node (ref "R10") (pin "2") (pinfunction "2_2") (pintype "passive"))
      (node (ref "R17") (pin "2") (pinfunction "2_2") (pintype "passive"))
      (node (ref "R18") (pin "2") (pinfunction "2_2") (pintype "passive"))
      (node (ref "R19") (pin "2") (pinfunction "2_2") (pintype "passive"))
      (node (ref "R2") (pin "2") (pinfunction "2_2") (pintype "passive"))
      (node (ref "R21") (pin "2") (pinfunction "2_2") (pintype "passive"))
      (node (ref "R23") (pin "2") (pinfunction "2_2") (pintype "passive"))
      (node (ref "R25") (pin "2") (pinfunction "2_2") (pintype "passive"))
      (node (ref "R3") (pin "2") (pinfunction "2_2") (pintype "passive"))
      (node (ref "R8") (pin "2") (pinfunction "2_2") (pintype "passive"))
      (node (ref "RN1") (pin "5") (pinfunction "5_5") (pintype "passive"))
      (node (ref "RN1") (pin "6") (pinfunction "6_6") (pintype "passive"))
      (node (ref "RN1") (pin "7") (pinfunction "7_7") (pintype "passive"))
      (node (ref "RN1") (pin "8") (pinfunction "8_8") (pintype "passive"))
      (node (ref "U1") (pin "8") (pinfunction "VCC_8") (pintype "passive"))
      (node (ref "U3") (pin "2") (pinfunction "Out_2") (pintype "passive"))
      (node (ref "U3") (pin "4") (pinfunction "TAB_4") (pintype "passive"))
      (node (ref "U4") (pin "1") (pinfunction "VBAT_1") (pintype "passive"))
      (node (ref "U4") (pin "13") (pinfunction "VDDA_13") (pintype "passive"))
      (node (ref "U4") (pin "19") (pinfunction "VDD_4_19") (pintype "passive"))
      (node (ref "U4") (pin "32") (pinfunction "VDD_1_32") (pintype "passive"))
      (node (ref "U4") (pin "48") (pinfunction "VDD_2_48") (pintype "passive"))
      (node (ref "U4") (pin "64") (pinfunction "VDD_3_64") (pintype "passive"))
    )
    (net (code "2") (name "+5V") (class "Default")
      (node (ref "C12") (pin "2") (pinfunction "2_2") (pintype "passive"))
      (node (ref "C13") (pin "2") (pinfunction "2_2") (pintype "passive"))
      (node (ref "C20") (pin "2") (pinfunction "2_2") (pintype "passive"))
      (node (ref "C21") (pin "2") (pinfunction "2_2") (pintype "passive"))
      (node (ref "C25") (pin "1") (pinfunction "1_1") (pintype "passive"))
      (node (ref "C26") (pin "2") (pinfunction "2_2") (pintype "passive"))
      (node (ref "C28") (pin "2") (pinfunction "2_2") (pintype "passive"))
      (node (ref "C29") (pin "2") (pinfunction "2_2") (pintype "passive"))
      (node (ref "C36") (pin "2") (pinfunction "2_2") (pintype "passive"))
      (node (ref "CN11") (pin "4") (pinfunction "4_4") (pintype "passive"))
      (node (ref "CN2") (pin "1") (pinfunction "1_1") (pintype "passive"))
      (node (ref "H2") (pin "5") (pinfunction "5_5") (pintype "passive"))
      (node (ref "L1") (pin "2") (pinfunction "2_2") (pintype "passive"))
      (node (ref "P1") (pin "1") (pinfunction "1_1") (pintype "passive"))
      (node (ref "R12") (pin "2") (pinfunction "2_2") (pintype "passive"))
      (node (ref "U3") (pin "3") (pinfunction "In_3") (pintype "passive"))
      (node (ref "U5") (pin "5") (pinfunction "VCC_5") (pintype "passive"))
      (node (ref "U6") (pin "14") (pinfunction "VCC_14") (pintype "passive"))
    )
    (net (code "3") (name "/A1") (class "Default")
      (node (ref "P1") (pin "5") (pinfunction "5_5") (pintype "passive"))
      (node (ref "U4") (pin "62") (pinfunction "PB9_62") (pintype "passive"))
    )
    (net (code "4") (name "/A3") (class "Default")
      (node (ref "P1") (pin "4") (pinfunction "4_4") (pintype "passive"))
      (node (ref "U4") (pin "61") (pinfunction "PB8_61") (pintype "passive"))
    )
    (net (code "5") (name "/BED") (class "Default")
      (node (ref "R40") (pin "1") (pinfunction "1_1") (pintype "passive"))
      (node (ref "U6") (pin "11") (pinfunction "4Y_11") (pintype "passive"))
    )
    (net (code "6") (name "/BED-PWM") (class "Default")
      (node (ref "RN2") (pin "5") (pinfunction "5_5") (pintype "passive"))
      (node (ref "U4") (pin "40") (pinfunction "PC9_40") (pintype "passive"))
      (node (ref "U6") (pin "12") (pinfunction "4A_12") (pintype "passive"))
    )
    (net (code "7") (name "/BED_CT") (class "Default")
      (node (ref "CN12") (pin "1") (pinfunction "1_1") (pintype "passive"))
      (node (ref "LED3") (pin "2") (pinfunction "2_2") (pintype "passive"))
      (node (ref "Q3") (pin "2") (pinfunction "D_2") (pintype "passive"))
    )
    (net (code "8") (name "/BEEPER") (class "Default")
      (node (ref "P1") (pin "10") (pinfunction "10_10") (pintype "passive"))
      (node (ref "U4") (pin "57") (pinfunction "PB5_57") (pintype "passive"))
    )
    (net (code "9") (name "/BOOT0") (class "Default")
      (node (ref "H3") (pin "2") (pinfunction "2_2") (pintype "passive"))
      (node (ref "R1") (pin "1") (pinfunction "1_1") (pintype "passive"))
      (node (ref "U4") (pin "60") (pinfunction "BOOT0_60") (pintype "passive"))
    )
    (net (code "10") (name "/BTN-ENC") (class "Default")
      (node (ref "P1") (pin "9") (pinfunction "9_9") (pintype "passive"))
      (node (ref "U4") (pin "50") (pinfunction "PA15_50") (pintype "passive"))
    )
    (net (code "11") (name "/CD-CS") (class "Default")
      (node (ref "CARD1") (pin "2") (pinfunction "CDDAT3(CS)_2") (pintype "passive"))
      (node (ref "H4") (pin "4") (pinfunction "4_4") (pintype "passive"))
      (node (ref "RN1") (pin "4") (pinfunction "4_4") (pintype "passive"))
      (node (ref "U4") (pin "20") (pinfunction "PA4_20") (pintype "passive"))
    )
    (net (code "12") (name "/E0-DIR") (class "Default")
      (node (ref "P2") (pin "8") (pinfunction "8_8") (pintype "passive"))
      (node (ref "RN3") (pin "4") (pinfunction "4_4") (pintype "passive"))
    )
    (net (code "13") (name "/E0-EN") (class "Default")
      (node (ref "P2") (pin "1") (pinfunction "1_1") (pintype "passive"))
      (node (ref "RN3") (pin "2") (pinfunction "2_2") (pintype "passive"))
    )
    (net (code "14") (name "/E0-STOP") (class "Default")
      (node (ref "R26") (pin "1") (pinfunction "1_1") (pintype "passive"))
      (node (ref "U4") (pin "4") (pinfunction "PC15-OSC32_OUT_4") (pintype "passive"))
    )
    (net (code "15") (name "/E0-STP") (class "Default")
      (node (ref "P2") (pin "7") (pinfunction "7_7") (pintype "passive"))
      (node (ref "RN3") (pin "3") (pinfunction "3_3") (pintype "passive"))
    )
    (net (code "16") (name "/E0DIR") (class "Default")
      (node (ref "RN3") (pin "5") (pinfunction "5_5") (pintype "passive"))
      (node (ref "U4") (pin "56") (pinfunction "PB4_56") (pintype "passive"))
    )
    (net (code "17") (name "/E0EN") (class "Default")
      (node (ref "RN3") (pin "7") (pinfunction "7_7") (pintype "passive"))
      (node (ref "U4") (pin "54") (pinfunction "PD2_54") (pintype "passive"))
    )
    (net (code "18") (name "/E0STP") (class "Default")
      (node (ref "RN3") (pin "6") (pinfunction "6_6") (pintype "passive"))
      (node (ref "U4") (pin "55") (pinfunction "PB3_55") (pintype "passive"))
    )
    (net (code "19") (name "/FAN") (class "Default")
      (node (ref "R37") (pin "1") (pinfunction "1_1") (pintype "passive"))
      (node (ref "U6") (pin "6") (pinfunction "2Y_6") (pintype "passive"))
    )
    (net (code "20") (name "/FAN-PWM") (class "Default")
      (node (ref "RN2") (pin "7") (pinfunction "7_7") (pintype "passive"))
      (node (ref "U4") (pin "38") (pinfunction "PC7_38") (pintype "passive"))
      (node (ref "U6") (pin "5") (pinfunction "2A_5") (pintype "passive"))
    )
    (net (code "21") (name "/FAN0") (class "Default")
      (node (ref "R38") (pin "1") (pinfunction "1_1") (pintype "passive"))
      (node (ref "U6") (pin "3") (pinfunction "1Y_3") (pintype "passive"))
    )
    (net (code "22") (name "/FAN0-PWM") (class "Default")
      (node (ref "RN2") (pin "8") (pinfunction "8_8") (pintype "passive"))
      (node (ref "U4") (pin "37") (pinfunction "PC6_37") (pintype "passive"))
      (node (ref "U6") (pin "2") (pinfunction "1A_2") (pintype "passive"))
    )
    (net (code "23") (name "/HE0") (class "Default")
      (node (ref "R39") (pin "1") (pinfunction "1_1") (pintype "passive"))
      (node (ref "U6") (pin "8") (pinfunction "3Y_8") (pintype "passive"))
    )
    (net (code "24") (name "/HE0-PWM") (class "Default")
      (node (ref "RN2") (pin "6") (pinfunction "6_6") (pintype "passive"))
      (node (ref "U4") (pin "39") (pinfunction "PC8_39") (pintype "passive"))
      (node (ref "U6") (pin "9") (pinfunction "3A_9") (pintype "passive"))
    )
    (net (code "25") (name "/HE0_CT") (class "Default")
      (node (ref "CN12") (pin "2") (pinfunction "2_2") (pintype "passive"))
      (node (ref "LED4") (pin "2") (pinfunction "2_2") (pintype "passive"))
      (node (ref "Q2") (pin "2") (pinfunction "D_2") (pintype "passive"))
    )
    (net (code "26") (name "/LCD-EN") (class "Default")
      (node (ref "P1") (pin "3") (pinfunction "3_3") (pintype "passive"))
      (node (ref "U4") (pin "36") (pinfunction "PB15_36") (pintype "passive"))
    )
    (net (code "27") (name "/NEO") (class "Default")
      (node (ref "R11") (pin "2") (pinfunction "2_2") (pintype "passive"))
      (node (ref "U4") (pin "41") (pinfunction "PA8_41") (pintype "passive"))
      (node (ref "U5") (pin "1") (pinfunction "1A_1") (pintype "passive"))
    )
    (net (code "28") (name "/PC12") (class "Default")
      (node (ref "CN1") (pin "3") (pinfunction "3_3") (pintype "passive"))
      (node (ref "U4") (pin "53") (pinfunction "PC12_53") (pintype "passive"))
    )
    (net (code "29") (name "/PROBE") (class "Default")
      (node (ref "CN11") (pin "1") (pinfunction "1_1") (pintype "passive"))
      (node (ref "U4") (pin "3") (pinfunction "PC14-OSC32_IN_3") (pintype "passive"))
    )
    (net (code "30") (name "/PS-ON") (class "Default")
      (node (ref "CN1") (pin "1") (pinfunction "1_1") (pintype "passive"))
      (node (ref "U4") (pin "2") (pinfunction "PC13-TAMPER-RTC_2") (pintype "passive"))
    )
    (net (code "31") (name "/RESET") (class "Default")
      (node (ref "C3") (pin "1") (pinfunction "1_1") (pintype "passive"))
      (node (ref "H2") (pin "1") (pinfunction "1_1") (pintype "passive"))
      (node (ref "P1") (pin "7") (pinfunction "7_7") (pintype "passive"))
      (node (ref "SW1") (pin "1") (pinfunction "1_1") (pintype "passive"))
      (node (ref "SW1") (pin "2") (pinfunction "2_2") (pintype "passive"))
      (node (ref "U4") (pin "7") (pinfunction "NRST_7") (pintype "passive"))
    )
    (net (code "32") (name "/RX1") (class "Default")
      (node (ref "P1") (pin "6") (pinfunction "6_6") (pintype "passive"))
      (node (ref "U4") (pin "43") (pinfunction "PA10_43") (pintype "passive"))
    )
    (net (code "33") (name "/RX2") (class "Default")
      (node (ref "H2") (pin "2") (pinfunction "2_2") (pintype "passive"))
      (node (ref "U4") (pin "17") (pinfunction "PA3_17") (pintype "passive"))
    )
    (net (code "34") (name "/RX4") (class "Default")
      (node (ref "R31") (pin "1") (pinfunction "1_1") (pintype "passive"))
      (node (ref "U4") (pin "52") (pinfunction "PC11_52") (pintype "passive"))
    )
    (net (code "35") (name "/SCL1") (class "Default")
      (node (ref "R2") (pin "1") (pinfunction "1_1") (pintype "passive"))
      (node (ref "U1") (pin "6") (pinfunction "SCL_6") (pintype "passive"))
      (node (ref "U4") (pin "58") (pinfunction "PB6_58") (pintype "passive"))
    )
    (net (code "36") (name "/SD-DET") (class "Default")
      (node (ref "CARD1") (pin "9") (pinfunction "CD_9") (pintype "passive"))
      (node (ref "R10") (pin "1") (pinfunction "1_1") (pintype "passive"))
      (node (ref "U4") (pin "24") (pinfunction "PC4_24") (pintype "passive"))
    )
    (net (code "37") (name "/SDA1") (class "Default")
      (node (ref "R3") (pin "1") (pinfunction "1_1") (pintype "passive"))
      (node (ref "U1") (pin "5") (pinfunction "SDA_5") (pintype "passive"))
      (node (ref "U4") (pin "59") (pinfunction "PB7_59") (pintype "passive"))
    )
    (net (code "38") (name "/SERVOS") (class "Default")
      (node (ref "CN11") (pin "3") (pinfunction "3_3") (pintype "passive"))
      (node (ref "U4") (pin "15") (pinfunction "PA1_15") (pintype "passive"))
    )
    (net (code "39") (name "/SPI1-MISO") (class "Default")
      (node (ref "CARD1") (pin "7") (pinfunction "DAT0(D0)_7") (pintype "passive"))
      (node (ref "H4") (pin "1") (pinfunction "1_1") (pintype "passive"))
      (node (ref "RN1") (pin "1") (pinfunction "1_1") (pintype "passive"))
      (node (ref "U4") (pin "22") (pinfunction "PA6_22") (pintype "passive"))
    )
    (net (code "40") (name "/SPI1-MOSI") (class "Default")
      (node (ref "CARD1") (pin "3") (pinfunction "CMD(DI)_3") (pintype "passive"))
      (node (ref "H4") (pin "3") (pinfunction "3_3") (pintype "passive"))
      (node (ref "RN1") (pin "3") (pinfunction "3_3") (pintype "passive"))
      (node (ref "U4") (pin "23") (pinfunction "PA7_23") (pintype "passive"))
    )
    (net (code "41") (name "/SPI1-SCK") (class "Default")
      (node (ref "CARD1") (pin "5") (pinfunction "CLK(SCLK)_5") (pintype "passive"))
      (node (ref "H4") (pin "2") (pinfunction "2_2") (pintype "passive"))
      (node (ref "RN1") (pin "2") (pinfunction "2_2") (pintype "passive"))
      (node (ref "U4") (pin "21") (pinfunction "PA5_21") (pintype "passive"))
    )
    (net (code "42") (name "/SWCLK") (class "Default")
      (node (ref "H1") (pin "2") (pinfunction "2_2") (pintype "passive"))
      (node (ref "U4") (pin "49") (pinfunction "PA14_49") (pintype "passive"))
    )
    (net (code "43") (name "/SWDIO") (class "Default")
      (node (ref "H1") (pin "3") (pinfunction "3_3") (pintype "passive"))
      (node (ref "U4") (pin "46") (pinfunction "PA13_46") (pintype "passive"))
    )
    (net (code "44") (name "/TH0") (class "Default")
      (node (ref "R15") (pin "1") (pinfunction "1_1") (pintype "passive"))
      (node (ref "U4") (pin "14") (pinfunction "PA0-WKUP_14") (pintype "passive"))
    )
    (net (code "45") (name "/THB") (class "Default")
      (node (ref "R16") (pin "1") (pinfunction "1_1") (pintype "passive"))
      (node (ref "U4") (pin "11") (pinfunction "PC3_11") (pintype "passive"))
    )
    (net (code "46") (name "/TX1") (class "Default")
      (node (ref "P1") (pin "8") (pinfunction "8_8") (pintype "passive"))
      (node (ref "U4") (pin "42") (pinfunction "PA9_42") (pintype "passive"))
    )
    (net (code "47") (name "/TX2") (class "Default")
      (node (ref "H2") (pin "3") (pinfunction "3_3") (pintype "passive"))
      (node (ref "U4") (pin "16") (pinfunction "PA2_16") (pintype "passive"))
    )
    (net (code "48") (name "/TX4") (class "Default")
      (node (ref "R27") (pin "1") (pinfunction "1_1") (pintype "passive"))
      (node (ref "U4") (pin "51") (pinfunction "PC10_51") (pintype "passive"))
    )
    (net (code "49") (name "/UART") (class "Default")
      (node (ref "P2") (pin "4") (pinfunction "4_4") (pintype "passive"))
      (node (ref "P4") (pin "4") (pinfunction "4_4") (pintype "passive"))
      (node (ref "P6") (pin "4") (pinfunction "4_4") (pintype "passive"))
      (node (ref "P8") (pin "4") (pinfunction "4_4") (pintype "passive"))
      (node (ref "R31") (pin "2") (pinfunction "2_2") (pintype "passive"))
      (node (ref "R33") (pin "2") (pinfunction "2_2") (pintype "passive"))
    )
    (net (code "50") (name "/USB_DN") (class "Default")
      (node (ref "R6") (pin "1") (pinfunction "1_1") (pintype "passive"))
      (node (ref "U4") (pin "44") (pinfunction "PA11_44") (pintype "passive"))
    )
    (net (code "51") (name "/USB_DP") (class "Default")
      (node (ref "R5") (pin "1") (pinfunction "1_1") (pintype "passive"))
      (node (ref "R8") (pin "1") (pinfunction "1_1") (pintype "passive"))
      (node (ref "U4") (pin "45") (pinfunction "PA12_45") (pintype "passive"))
    )
    (net (code "52") (name "/X-DIR") (class "Default")
      (node (ref "P4") (pin "8") (pinfunction "8_8") (pintype "passive"))
      (node (ref "RN4") (pin "4") (pinfunction "4_4") (pintype "passive"))
    )
    (net (code "53") (name "/X-EN") (class "Default")
      (node (ref "P4") (pin "1") (pinfunction "1_1") (pintype "passive"))
      (node (ref "RN4") (pin "2") (pinfunction "2_2") (pintype "passive"))
    )
    (net (code "54") (name "/X-STOP") (class "Default")
      (node (ref "R20") (pin "1") (pinfunction "1_1") (pintype "passive"))
      (node (ref "U4") (pin "8") (pinfunction "PC0_8") (pintype "passive"))
    )
    (net (code "55") (name "/X-STP") (class "Default")
      (node (ref "P4") (pin "7") (pinfunction "7_7") (pintype "passive"))
      (node (ref "RN4") (pin "3") (pinfunction "3_3") (pintype "passive"))
    )
    (net (code "56") (name "/XDIR") (class "Default")
      (node (ref "RN4") (pin "5") (pinfunction "5_5") (pintype "passive"))
      (node (ref "U4") (pin "33") (pinfunction "PB12_33") (pintype "passive"))
    )
    (net (code "57") (name "/XEN") (class "Default")
      (node (ref "RN4") (pin "7") (pinfunction "7_7") (pintype "passive"))
      (node (ref "U4") (pin "35") (pinfunction "PB14_35") (pintype "passive"))
    )
    (net (code "58") (name "/XSTP") (class "Default")
      (node (ref "RN4") (pin "6") (pinfunction "6_6") (pintype "passive"))
      (node (ref "U4") (pin "34") (pinfunction "PB13_34") (pintype "passive"))
    )
    (net (code "59") (name "/Y-DIR") (class "Default")
      (node (ref "P6") (pin "8") (pinfunction "8_8") (pintype "passive"))
      (node (ref "RN5") (pin "4") (pinfunction "4_4") (pintype "passive"))
    )
    (net (code "60") (name "/Y-EN") (class "Default")
      (node (ref "P6") (pin "1") (pinfunction "1_1") (pintype "passive"))
      (node (ref "RN5") (pin "2") (pinfunction "2_2") (pintype "passive"))
    )
    (net (code "61") (name "/Y-STOP") (class "Default")
      (node (ref "R22") (pin "1") (pinfunction "1_1") (pintype "passive"))
      (node (ref "U4") (pin "9") (pinfunction "PC1_9") (pintype "passive"))
    )
    (net (code "62") (name "/Y-STP") (class "Default")
      (node (ref "P6") (pin "7") (pinfunction "7_7") (pintype "passive"))
      (node (ref "RN5") (pin "3") (pinfunction "3_3") (pintype "passive"))
    )
    (net (code "63") (name "/YDIR") (class "Default")
      (node (ref "RN5") (pin "5") (pinfunction "5_5") (pintype "passive"))
      (node (ref "U4") (pin "28") (pinfunction "PB2_28") (pintype "passive"))
    )
    (net (code "64") (name "/YEN") (class "Default")
      (node (ref "RN5") (pin "7") (pinfunction "7_7") (pintype "passive"))
      (node (ref "U4") (pin "30") (pinfunction "PB11_30") (pintype "passive"))
    )
    (net (code "65") (name "/YSTP") (class "Default")
      (node (ref "RN5") (pin "6") (pinfunction "6_6") (pintype "passive"))
      (node (ref "U4") (pin "29") (pinfunction "PB10_29") (pintype "passive"))
    )
    (net (code "66") (name "/Z-DIR") (class "Default")
      (node (ref "P8") (pin "8") (pinfunction "8_8") (pintype "passive"))
      (node (ref "RN6") (pin "4") (pinfunction "4_4") (pintype "passive"))
    )
    (net (code "67") (name "/Z-EN") (class "Default")
      (node (ref "P8") (pin "1") (pinfunction "1_1") (pintype "passive"))
      (node (ref "RN6") (pin "2") (pinfunction "2_2") (pintype "passive"))
    )
    (net (code "68") (name "/Z-STOP") (class "Default")
      (node (ref "R24") (pin "1") (pinfunction "1_1") (pintype "passive"))
      (node (ref "U4") (pin "10") (pinfunction "PC2_10") (pintype "passive"))
    )
    (net (code "69") (name "/Z-STP") (class "Default")
      (node (ref "P8") (pin "7") (pinfunction "7_7") (pintype "passive"))
      (node (ref "RN6") (pin "3") (pinfunction "3_3") (pintype "passive"))
    )
    (net (code "70") (name "/ZDIR") (class "Default")
      (node (ref "RN6") (pin "5") (pinfunction "5_5") (pintype "passive"))
      (node (ref "U4") (pin "25") (pinfunction "PC5_25") (pintype "passive"))
    )
    (net (code "71") (name "/ZEN") (class "Default")
      (node (ref "RN6") (pin "7") (pinfunction "7_7") (pintype "passive"))
      (node (ref "U4") (pin "27") (pinfunction "PB1_27") (pintype "passive"))
    )
    (net (code "72") (name "/ZSTP") (class "Default")
      (node (ref "RN6") (pin "6") (pinfunction "6_6") (pintype "passive"))
      (node (ref "U4") (pin "26") (pinfunction "PB0_26") (pintype "passive"))
    )
    (net (code "73") (name "GND") (class "Default")
      (node (ref "C1") (pin "2") (pinfunction "2_2") (pintype "passive"))
      (node (ref "C10") (pin "1") (pinfunction "1_1") (pintype "passive"))
      (node (ref "C11") (pin "1") (pinfunction "1_1") (pintype "passive"))
      (node (ref "C12") (pin "1") (pinfunction "1_1") (pintype "passive"))
      (node (ref "C13") (pin "1") (pinfunction "1_1") (pintype "passive"))
      (node (ref "C15") (pin "1") (pinfunction "1_1") (pintype "passive"))
      (node (ref "C16") (pin "1") (pinfunction "1_1") (pintype "passive"))
      (node (ref "C17") (pin "1") (pinfunction "1_1") (pintype "passive"))
      (node (ref "C19") (pin "1") (pinfunction "1_1") (pintype "passive"))
      (node (ref "C2") (pin "2") (pinfunction "2_2") (pintype "passive"))
      (node (ref "C20") (pin "1") (pinfunction "1_1") (pintype "passive"))
      (node (ref "C21") (pin "1") (pinfunction "1_1") (pintype "passive"))
      (node (ref "C23") (pin "1") (pinfunction "1_1") (pintype "passive"))
      (node (ref "C24") (pin "1") (pinfunction "1_1") (pintype "passive"))
      (node (ref "C25") (pin "2") (pinfunction "2_2") (pintype "passive"))
      (node (ref "C26") (pin "1") (pinfunction "1_1") (pintype "passive"))
      (node (ref "C27") (pin "2") (pinfunction "2_2") (pintype "passive"))
      (node (ref "C28") (pin "1") (pinfunction "1_1") (pintype "passive"))
      (node (ref "C29") (pin "1") (pinfunction "1_1") (pintype "passive"))
      (node (ref "C3") (pin "2") (pinfunction "2_2") (pintype "passive"))
      (node (ref "C30") (pin "1") (pinfunction "1_1") (pintype "passive"))
      (node (ref "C31") (pin "1") (pinfunction "1_1") (pintype "passive"))
      (node (ref "C32") (pin "1") (pinfunction "1_1") (pintype "passive"))
      (node (ref "C33") (pin "1") (pinfunction "1_1") (pintype "passive"))
      (node (ref "C34") (pin "1") (pinfunction "1_1") (pintype "passive"))
      (node (ref "C35") (pin "1") (pinfunction "1_1") (pintype "passive"))
      (node (ref "C36") (pin "1") (pinfunction "1_1") (pintype "passive"))
      (node (ref "C37") (pin "2") (pinfunction "2_2") (pintype "passive"))
      (node (ref "C38") (pin "1") (pinfunction "1_1") (pintype "passive"))
      (node (ref "C39") (pin "2") (pinfunction "2_2") (pintype "passive"))
      (node (ref "C4") (pin "1") (pinfunction "1_1") (pintype "passive"))
      (node (ref "C40") (pin "1") (pinfunction "1_1") (pintype "passive"))
      (node (ref "C41") (pin "2") (pinfunction "2_2") (pintype "passive"))
      (node (ref "C42") (pin "1") (pinfunction "1_1") (pintype "passive"))
      (node (ref "C43") (pin "2") (pinfunction "2_2") (pintype "passive"))
      (node (ref "C44") (pin "1") (pinfunction "1_1") (pintype "passive"))
      (node (ref "C5") (pin "1") (pinfunction "1_1") (pintype "passive"))
      (node (ref "C6") (pin "1") (pinfunction "1_1") (pintype "passive"))
      (node (ref "C7") (pin "1") (pinfunction "1_1") (pintype "passive"))
      (node (ref "C8") (pin "1") (pinfunction "1_1") (pintype "passive"))
      (node (ref "C9") (pin "1") (pinfunction "1_1") (pintype "passive"))
      (node (ref "CARD1") (pin "10") (pinfunction "GND_10") (pintype "passive"))
      (node (ref "CARD1") (pin "11") (pinfunction "GND_11") (pintype "passive"))
      (node (ref "CARD1") (pin "12") (pinfunction "GND_12") (pintype "passive"))
      (node (ref "CARD1") (pin "13") (pinfunction "GND_13") (pintype "passive"))
      (node (ref "CARD1") (pin "6") (pinfunction "VSS_6") (pintype "passive"))
      (node (ref "CN1") (pin "2") (pinfunction "2_2") (pintype "passive"))
      (node (ref "CN11") (pin "2") (pinfunction "2_2") (pintype "passive"))
      (node (ref "CN11") (pin "5") (pinfunction "5_5") (pintype "passive"))
      (node (ref "CN12") (pin "6") (pinfunction "6_6") (pintype "passive"))
      (node (ref "CN2") (pin "3") (pinfunction "3_3") (pintype "passive"))
      (node (ref "CN4") (pin "2") (pinfunction "2_2") (pintype "passive"))
      (node (ref "CN5") (pin "2") (pinfunction "2_2") (pintype "passive"))
      (node (ref "CN6") (pin "2") (pinfunction "2_2") (pintype "passive"))
      (node (ref "CN7") (pin "2") (pinfunction "2_2") (pintype "passive"))
      (node (ref "CN8") (pin "2") (pinfunction "2_2") (pintype "passive"))
      (node (ref "CN9") (pin "2") (pinfunction "2_2") (pintype "passive"))
      (node (ref "D1") (pin "1") (pinfunction "1_1") (pintype "passive"))
      (node (ref "D10") (pin "1") (pinfunction "1_1") (pintype "passive"))
      (node (ref "D11") (pin "1") (pinfunction "A_1") (pintype "passive"))
      (node (ref "D11") (pin "2") (pinfunction "A_2") (pintype "passive"))
      (node (ref "D3") (pin "1") (pinfunction "A_1") (pintype "passive"))
      (node (ref "D4") (pin "1") (pinfunction "1_1") (pintype "passive"))
      (node (ref "D5") (pin "1") (pinfunction "1_1") (pintype "passive"))
      (node (ref "D6") (pin "1") (pinfunction "1_1") (pintype "passive"))
      (node (ref "D7") (pin "1") (pinfunction "1_1") (pintype "passive"))
      (node (ref "D8") (pin "1") (pinfunction "1_1") (pintype "passive"))
      (node (ref "D9") (pin "1") (pinfunction "1_1") (pintype "passive"))
      (node (ref "H1") (pin "1") (pinfunction "1_1") (pintype "passive"))
      (node (ref "H2") (pin "4") (pinfunction "4_4") (pintype "passive"))
      (node (ref "P1") (pin "2") (pinfunction "2_2") (pintype "passive"))
      (node (ref "P3") (pin "2") (pinfunction "2_2") (pintype "passive"))
      (node (ref "P3") (pin "8") (pinfunction "8_8") (pintype "passive"))
      (node (ref "P4") (pin "2") (pinfunction "2_2") (pintype "passive"))
      (node (ref "P4") (pin "3") (pinfunction "3_3") (pintype "passive"))
      (node (ref "P5") (pin "2") (pinfunction "2_2") (pintype "passive"))
      (node (ref "P5") (pin "8") (pinfunction "8_8") (pintype "passive"))
      (node (ref "P6") (pin "2") (pinfunction "2_2") (pintype "passive"))
      (node (ref "P7") (pin "2") (pinfunction "2_2") (pintype "passive"))
      (node (ref "P7") (pin "8") (pinfunction "8_8") (pintype "passive"))
      (node (ref "P8") (pin "3") (pinfunction "3_3") (pintype "passive"))
      (node (ref "P9") (pin "2") (pinfunction "2_2") (pintype "passive"))
      (node (ref "P9") (pin "8") (pinfunction "8_8") (pintype "passive"))
      (node (ref "Q2") (pin "3") (pinfunction "S_3") (pintype "passive"))
      (node (ref "Q3") (pin "3") (pinfunction "S_3") (pintype "passive"))
      (node (ref "Q4") (pin "2") (pinfunction "S_2") (pintype "passive"))
      (node (ref "Q5") (pin "2") (pinfunction "S_2") (pintype "passive"))
      (node (ref "R1") (pin "2") (pinfunction "2_2") (pintype "passive"))
      (node (ref "R11") (pin "1") (pinfunction "1_1") (pintype "passive"))
      (node (ref "R13") (pin "1") (pinfunction "1_1") (pintype "passive"))
      (node (ref "R14") (pin "1") (pinfunction "1_1") (pintype "passive"))
      (node (ref "R28") (pin "1") (pinfunction "1_1") (pintype "passive"))
      (node (ref "R32") (pin "1") (pinfunction "1_1") (pintype "passive"))
      (node (ref "R34") (pin "1") (pinfunction "1_1") (pintype "passive"))
      (node (ref "R36") (pin "1") (pinfunction "1_1") (pintype "passive"))
      (node (ref "R4") (pin "2") (pinfunction "2_2") (pintype "passive"))
      (node (ref "RN2") (pin "1") (pinfunction "1_1") (pintype "passive"))
      (node (ref "RN2") (pin "2") (pinfunction "2_2") (pintype "passive"))
      (node (ref "RN2") (pin "3") (pinfunction "3_3") (pintype "passive"))
      (node (ref "RN2") (pin "4") (pinfunction "4_4") (pintype "passive"))
      (node (ref "SW1") (pin "3") (pinfunction "3_3") (pintype "passive"))
      (node (ref "SW1") (pin "4") (pinfunction "4_4") (pintype "passive"))
      (node (ref "U1") (pin "1") (pinfunction "A0_1") (pintype "passive"))
      (node (ref "U1") (pin "2") (pinfunction "A1_2") (pintype "passive"))
      (node (ref "U1") (pin "3") (pinfunction "A2_3") (pintype "passive"))
      (node (ref "U1") (pin "4") (pinfunction "GND_4") (pintype "passive"))
      (node (ref "U1") (pin "7") (pinfunction "WP_7") (pintype "passive"))
      (node (ref "U2") (pin "4") (pinfunction "GND_4") (pintype "passive"))
      (node (ref "U2") (pin "9") (pinfunction "EP_9") (pintype "passive"))
      (node (ref "U3") (pin "1") (pinfunction "GND_1") (pintype "passive"))
      (node (ref "U4") (pin "12") (pinfunction "VSSA_12") (pintype "passive"))
      (node (ref "U4") (pin "18") (pinfunction "VSS_4_18") (pintype "passive"))
      (node (ref "U4") (pin "31") (pinfunction "VSS_1_31") (pintype "passive"))
      (node (ref "U4") (pin "47") (pinfunction "VSS_2_47") (pintype "passive"))
      (node (ref "U4") (pin "63") (pinfunction "VSS_3_63") (pintype "passive"))
      (node (ref "U5") (pin "2") (pinfunction "GND_2") (pintype "passive"))
      (node (ref "U6") (pin "1") (pinfunction "1OE#_1") (pintype "passive"))
      (node (ref "U6") (pin "10") (pinfunction "3OE#_10") (pintype "passive"))
      (node (ref "U6") (pin "13") (pinfunction "4OE#_13") (pintype "passive"))
      (node (ref "U6") (pin "4") (pinfunction "2OE#_4") (pintype "passive"))
      (node (ref "U6") (pin "7") (pinfunction "GND_7") (pintype "passive"))
      (node (ref "USB1") (pin "5") (pinfunction "GND_5") (pintype "passive"))
      (node (ref "USB1") (pin "6") (pinfunction "SH1_6") (pintype "passive"))
      (node (ref "USB1") (pin "7") (pinfunction "SH2_7") (pintype "passive"))
      (node (ref "USB1") (pin "8") (pinfunction "SH3_8") (pintype "passive"))
      (node (ref "USB1") (pin "9") (pinfunction "SH4_9") (pintype "passive"))
      (node (ref "X1") (pin "2") (pinfunction "2_2") (pintype "passive"))
      (node (ref "X1") (pin "4") (pinfunction "4_4") (pintype "passive"))
    )
    (net (code "74") (name "Net-(C22-Pad1)") (class "Default")
      (node (ref "C22") (pin "1") (pinfunction "1_1") (pintype "passive"))
      (node (ref "R14") (pin "2") (pinfunction "2_2") (pintype "passive"))
    )
    (net (code "75") (name "Net-(C30-Pad2)") (class "Default")
      (node (ref "C30") (pin "2") (pinfunction "2_2") (pintype "passive"))
      (node (ref "CN4") (pin "1") (pinfunction "1_1") (pintype "passive"))
      (node (ref "D4") (pin "2") (pinfunction "2_2") (pintype "passive"))
      (node (ref "R15") (pin "2") (pinfunction "2_2") (pintype "passive"))
      (node (ref "R17") (pin "1") (pinfunction "1_1") (pintype "passive"))
    )
    (net (code "76") (name "Net-(C31-Pad2)") (class "Default")
      (node (ref "C31") (pin "2") (pinfunction "2_2") (pintype "passive"))
      (node (ref "CN5") (pin "1") (pinfunction "1_1") (pintype "passive"))
      (node (ref "D5") (pin "2") (pinfunction "2_2") (pintype "passive"))
      (node (ref "R16") (pin "2") (pinfunction "2_2") (pintype "passive"))
      (node (ref "R18") (pin "1") (pinfunction "1_1") (pintype "passive"))
    )
    (net (code "77") (name "Net-(C32-Pad2)") (class "Default")
      (node (ref "C32") (pin "2") (pinfunction "2_2") (pintype "passive"))
      (node (ref "CN6") (pin "1") (pinfunction "1_1") (pintype "passive"))
      (node (ref "D6") (pin "2") (pinfunction "2_2") (pintype "passive"))
      (node (ref "R19") (pin "1") (pinfunction "1_1") (pintype "passive"))
      (node (ref "R20") (pin "2") (pinfunction "2_2") (pintype "passive"))
    )
    (net (code "78") (name "Net-(C33-Pad2)") (class "Default")
      (node (ref "C33") (pin "2") (pinfunction "2_2") (pintype "passive"))
      (node (ref "CN7") (pin "1") (pinfunction "1_1") (pintype "passive"))
      (node (ref "D7") (pin "2") (pinfunction "2_2") (pintype "passive"))
      (node (ref "R21") (pin "1") (pinfunction "1_1") (pintype "passive"))
      (node (ref "R22") (pin "2") (pinfunction "2_2") (pintype "passive"))
    )
    (net (code "79") (name "Net-(C34-Pad2)") (class "Default")
      (node (ref "C34") (pin "2") (pinfunction "2_2") (pintype "passive"))
      (node (ref "CN8") (pin "1") (pinfunction "1_1") (pintype "passive"))
      (node (ref "D8") (pin "2") (pinfunction "2_2") (pintype "passive"))
      (node (ref "R23") (pin "1") (pinfunction "1_1") (pintype "passive"))
      (node (ref "R24") (pin "2") (pinfunction "2_2") (pintype "passive"))
    )
    (net (code "80") (name "Net-(C35-Pad2)") (class "Default")
      (node (ref "C35") (pin "2") (pinfunction "2_2") (pintype "passive"))
      (node (ref "CN9") (pin "1") (pinfunction "1_1") (pintype "passive"))
      (node (ref "D9") (pin "2") (pinfunction "2_2") (pintype "passive"))
      (node (ref "R25") (pin "1") (pinfunction "1_1") (pintype "passive"))
      (node (ref "R26") (pin "2") (pinfunction "2_2") (pintype "passive"))
    )
    (net (code "81") (name "Net-(CN3-Pad1)") (class "Default")
      (node (ref "CN3") (pin "1") (pinfunction "1_1") (pintype "passive"))
      (node (ref "P3") (pin "3") (pinfunction "3_3") (pintype "passive"))
    )
    (net (code "82") (name "Net-(CN3-Pad2)") (class "Default")
      (node (ref "CN3") (pin "2") (pinfunction "2_2") (pintype "passive"))
      (node (ref "P3") (pin "4") (pinfunction "4_4") (pintype "passive"))
    )
    (net (code "83") (name "Net-(CN3-Pad3)") (class "Default")
      (node (ref "CN3") (pin "3") (pinfunction "3_3") (pintype "passive"))
      (node (ref "P3") (pin "5") (pinfunction "5_5") (pintype "passive"))
    )
    (net (code "84") (name "Net-(CN3-Pad4)") (class "Default")
      (node (ref "CN3") (pin "4") (pinfunction "4_4") (pintype "passive"))
      (node (ref "P3") (pin "6") (pinfunction "6_6") (pintype "passive"))
    )
    (net (code "85") (name "Net-(CN12-Pad5)") (class "Default")
      (node (ref "CN12") (pin "5") (pinfunction "5_5") (pintype "passive"))
      (node (ref "F1") (pin "1") (pinfunction "1_1") (pintype "passive"))
    )
    (net (code "86") (name "Net-(CN15-Pad1)") (class "Default")
      (node (ref "CN15") (pin "1") (pinfunction "1_1") (pintype "passive"))
      (node (ref "P5") (pin "3") (pinfunction "3_3") (pintype "passive"))
    )
    (net (code "87") (name "Net-(CN15-Pad2)") (class "Default")
      (node (ref "CN15") (pin "2") (pinfunction "2_2") (pintype "passive"))
      (node (ref "P5") (pin "4") (pinfunction "4_4") (pintype "passive"))
    )
    (net (code "88") (name "Net-(CN15-Pad3)") (class "Default")
      (node (ref "CN15") (pin "3") (pinfunction "3_3") (pintype "passive"))
      (node (ref "P5") (pin "5") (pinfunction "5_5") (pintype "passive"))
    )
    (net (code "89") (name "Net-(CN15-Pad4)") (class "Default")
      (node (ref "CN15") (pin "4") (pinfunction "4_4") (pintype "passive"))
      (node (ref "P5") (pin "6") (pinfunction "6_6") (pintype "passive"))
    )
    (net (code "90") (name "Net-(CN16-Pad1)") (class "Default")
      (node (ref "CN16") (pin "1") (pinfunction "1_1") (pintype "passive"))
      (node (ref "P7") (pin "3") (pinfunction "3_3") (pintype "passive"))
    )
    (net (code "91") (name "Net-(CN16-Pad2)") (class "Default")
      (node (ref "CN16") (pin "2") (pinfunction "2_2") (pintype "passive"))
      (node (ref "P7") (pin "4") (pinfunction "4_4") (pintype "passive"))
    )
    (net (code "92") (name "Net-(CN16-Pad3)") (class "Default")
      (node (ref "CN16") (pin "3") (pinfunction "3_3") (pintype "passive"))
      (node (ref "P7") (pin "5") (pinfunction "5_5") (pintype "passive"))
    )
    (net (code "93") (name "Net-(CN16-Pad4)") (class "Default")
      (node (ref "CN16") (pin "4") (pinfunction "4_4") (pintype "passive"))
      (node (ref "P7") (pin "6") (pinfunction "6_6") (pintype "passive"))
    )
    (net (code "94") (name "Net-(CN17-Pad1)") (class "Default")
      (node (ref "CN17") (pin "1") (pinfunction "1_1") (pintype "passive"))
      (node (ref "P9") (pin "3") (pinfunction "3_3") (pintype "passive"))
    )
    (net (code "95") (name "Net-(CN17-Pad2)") (class "Default")
      (node (ref "CN17") (pin "2") (pinfunction "2_2") (pintype "passive"))
      (node (ref "P9") (pin "4") (pinfunction "4_4") (pintype "passive"))
    )
    (net (code "96") (name "Net-(CN17-Pad3)") (class "Default")
      (node (ref "CN17") (pin "3") (pinfunction "3_3") (pintype "passive"))
      (node (ref "P9") (pin "5") (pinfunction "5_5") (pintype "passive"))
    )
    (net (code "97") (name "Net-(CN17-Pad4)") (class "Default")
      (node (ref "CN17") (pin "4") (pinfunction "4_4") (pintype "passive"))
      (node (ref "P9") (pin "6") (pinfunction "6_6") (pintype "passive"))
    )
    (net (code "98") (name "Net-(D11-K)") (class "Default")
      (node (ref "C45") (pin "2") (pinfunction "2_2") (pintype "passive"))
      (node (ref "D11") (pin "3") (pinfunction "K_3") (pintype "passive"))
      (node (ref "L1") (pin "1") (pinfunction "1_1") (pintype "passive"))
      (node (ref "U2") (pin "3") (pinfunction "SW_3") (pintype "passive"))
    )
    (net (code "99") (name "Net-(LED1-C)") (class "Default")
      (node (ref "LED1") (pin "2") (pinfunction "C_2") (pintype "passive"))
      (node (ref "R4") (pin "1") (pinfunction "1_1") (pintype "passive"))
    )
    (net (code "100") (name "Net-(LED3-Pad1)") (class "Default")
      (node (ref "LED3") (pin "1") (pinfunction "1_1") (pintype "passive"))
      (node (ref "R30") (pin "1") (pinfunction "1_1") (pintype "passive"))
    )
    (net (code "101") (name "Net-(LED4-Pad1)") (class "Default")
      (node (ref "LED4") (pin "1") (pinfunction "1_1") (pintype "passive"))
      (node (ref "R29") (pin "1") (pinfunction "1_1") (pintype "passive"))
    )
    (net (code "102") (name "Net-(Q2-G)") (class "Default")
      (node (ref "Q2") (pin "1") (pinfunction "G_1") (pintype "passive"))
      (node (ref "R28") (pin "2") (pinfunction "2_2") (pintype "passive"))
      (node (ref "R39") (pin "2") (pinfunction "2_2") (pintype "passive"))
    )
    (net (code "103") (name "Net-(Q3-G)") (class "Default")
      (node (ref "Q3") (pin "1") (pinfunction "G_1") (pintype "passive"))
      (node (ref "R32") (pin "2") (pinfunction "2_2") (pintype "passive"))
      (node (ref "R40") (pin "2") (pinfunction "2_2") (pintype "passive"))
    )
    (net (code "104") (name "Net-(Q4-D)") (class "Default")
      (node (ref "CN13") (pin "1") (pinfunction "1_1") (pintype "passive"))
      (node (ref "Q4") (pin "3") (pinfunction "D_3") (pintype "passive"))
    )
    (net (code "105") (name "Net-(Q4-G)") (class "Default")
      (node (ref "Q4") (pin "1") (pinfunction "G_1") (pintype "passive"))
      (node (ref "R34") (pin "2") (pinfunction "2_2") (pintype "passive"))
      (node (ref "R37") (pin "2") (pinfunction "2_2") (pintype "passive"))
    )
    (net (code "106") (name "Net-(Q5-D)") (class "Default")
      (node (ref "CN14") (pin "1") (pinfunction "1_1") (pintype "passive"))
      (node (ref "Q5") (pin "3") (pinfunction "D_3") (pintype "passive"))
    )
    (net (code "107") (name "Net-(Q5-G)") (class "Default")
      (node (ref "Q5") (pin "1") (pinfunction "G_1") (pintype "passive"))
      (node (ref "R36") (pin "2") (pinfunction "2_2") (pintype "passive"))
      (node (ref "R38") (pin "2") (pinfunction "2_2") (pintype "passive"))
    )
    (net (code "108") (name "Net-(R27-Pad2)") (class "Default")
      (node (ref "R27") (pin "2") (pinfunction "2_2") (pintype "passive"))
      (node (ref "R33") (pin "1") (pinfunction "1_1") (pintype "passive"))
    )
    (net (code "109") (name "Net-(U2-BS)") (class "Default")
      (node (ref "C45") (pin "1") (pinfunction "1_1") (pintype "passive"))
      (node (ref "U2") (pin "1") (pinfunction "BS_1") (pintype "passive"))
    )
    (net (code "110") (name "Net-(U2-COMP)") (class "Default")
      (node (ref "C22") (pin "2") (pinfunction "2_2") (pintype "passive"))
      (node (ref "U2") (pin "6") (pinfunction "COMP_6") (pintype "passive"))
    )
    (net (code "111") (name "Net-(U2-FB)") (class "Default")
      (node (ref "R12") (pin "1") (pinfunction "1_1") (pintype "passive"))
      (node (ref "R13") (pin "2") (pinfunction "2_2") (pintype "passive"))
      (node (ref "U2") (pin "5") (pinfunction "FB_5") (pintype "passive"))
    )
    (net (code "112") (name "Net-(U2-SS)") (class "Default")
      (node (ref "C23") (pin "2") (pinfunction "2_2") (pintype "passive"))
      (node (ref "U2") (pin "8") (pinfunction "SS_8") (pintype "passive"))
    )
    (net (code "113") (name "Net-(U4A-PD0-OSC_IN)") (class "Default")
      (node (ref "C1") (pin "1") (pinfunction "1_1") (pintype "passive"))
      (node (ref "U4") (pin "5") (pinfunction "PD0-OSC_IN_5") (pintype "passive"))
      (node (ref "X1") (pin "3") (pinfunction "3_3") (pintype "passive"))
    )
    (net (code "114") (name "Net-(U4A-PD1-OSC_OUT)") (class "Default")
      (node (ref "C2") (pin "1") (pinfunction "1_1") (pintype "passive"))
      (node (ref "U4") (pin "6") (pinfunction "PD1-OSC_OUT_6") (pintype "passive"))
      (node (ref "X1") (pin "1") (pinfunction "1_1") (pintype "passive"))
    )
    (net (code "115") (name "Net-(U5-1Y)") (class "Default")
      (node (ref "CN2") (pin "2") (pinfunction "2_2") (pintype "passive"))
      (node (ref "U5") (pin "6") (pinfunction "1Y_6") (pintype "passive"))
    )
    (net (code "116") (name "Net-(USB1-D+)") (class "Default")
      (node (ref "D10") (pin "2") (pinfunction "2_2") (pintype "passive"))
      (node (ref "R5") (pin "2") (pinfunction "2_2") (pintype "passive"))
      (node (ref "USB1") (pin "3") (pinfunction "D+_3") (pintype "passive"))
    )
    (net (code "117") (name "Net-(USB1-D-)") (class "Default")
      (node (ref "D1") (pin "2") (pinfunction "2_2") (pintype "passive"))
      (node (ref "R6") (pin "2") (pinfunction "2_2") (pintype "passive"))
      (node (ref "USB1") (pin "2") (pinfunction "D-_2") (pintype "passive"))
    )
    (net (code "118") (name "VIN") (class "Default")
      (node (ref "C19") (pin "2") (pinfunction "2_2") (pintype "passive"))
      (node (ref "C24") (pin "2") (pinfunction "2_2") (pintype "passive"))
      (node (ref "C37") (pin "1") (pinfunction "1_1") (pintype "passive"))
      (node (ref "C38") (pin "2") (pinfunction "2_2") (pintype "passive"))
      (node (ref "C39") (pin "1") (pinfunction "1_1") (pintype "passive"))
      (node (ref "C40") (pin "2") (pinfunction "2_2") (pintype "passive"))
      (node (ref "C41") (pin "1") (pinfunction "1_1") (pintype "passive"))
      (node (ref "C42") (pin "2") (pinfunction "2_2") (pintype "passive"))
      (node (ref "C43") (pin "1") (pinfunction "1_1") (pintype "passive"))
      (node (ref "C44") (pin "2") (pinfunction "2_2") (pintype "passive"))
      (node (ref "CN12") (pin "3") (pinfunction "3_3") (pintype "passive"))
      (node (ref "CN12") (pin "4") (pinfunction "4_4") (pintype "passive"))
      (node (ref "CN13") (pin "2") (pinfunction "2_2") (pintype "passive"))
      (node (ref "CN14") (pin "2") (pinfunction "2_2") (pintype "passive"))
      (node (ref "D3") (pin "2") (pinfunction "K_2") (pintype "passive"))
      (node (ref "F1") (pin "2") (pinfunction "2_2") (pintype "passive"))
      (node (ref "P3") (pin "1") (pinfunction "1_1") (pintype "passive"))
      (node (ref "P5") (pin "1") (pinfunction "1_1") (pintype "passive"))
      (node (ref "P7") (pin "1") (pinfunction "1_1") (pintype "passive"))
      (node (ref "P9") (pin "1") (pinfunction "1_1") (pintype "passive"))
      (node (ref "R29") (pin "2") (pinfunction "2_2") (pintype "passive"))
      (node (ref "R30") (pin "2") (pinfunction "2_2") (pintype "passive"))
      (node (ref "U2") (pin "2") (pinfunction "IN_2") (pintype "passive"))
    )
    (net (code "119") (name "unconnected-(CARD1-DAT1(RSV)-Pad8)") (class "Default")
      (node (ref "CARD1") (pin "8") (pinfunction "DAT1(RSV)_8") (pintype "passive+no_connect"))
    )
    (net (code "120") (name "unconnected-(CARD1-DAT2(RSV)-Pad1)") (class "Default")
      (node (ref "CARD1") (pin "1") (pinfunction "DAT2(RSV)_1") (pintype "passive+no_connect"))
    )
    (net (code "121") (name "unconnected-(P2-Pad5)") (class "Default")
      (node (ref "P2") (pin "5") (pinfunction "5_5") (pintype "passive+no_connect"))
    )
    (net (code "122") (name "unconnected-(P2-Pad6)") (class "Default")
      (node (ref "P2") (pin "6") (pinfunction "6_6") (pintype "passive+no_connect"))
    )
    (net (code "123") (name "unconnected-(P4-Pad5)") (class "Default")
      (node (ref "P4") (pin "5") (pinfunction "5_5") (pintype "passive+no_connect"))
    )
    (net (code "124") (name "unconnected-(P4-Pad6)") (class "Default")
      (node (ref "P4") (pin "6") (pinfunction "6_6") (pintype "passive+no_connect"))
    )
    (net (code "125") (name "unconnected-(P6-Pad5)") (class "Default")
      (node (ref "P6") (pin "5") (pinfunction "5_5") (pintype "passive+no_connect"))
    )
    (net (code "126") (name "unconnected-(P6-Pad6)") (class "Default")
      (node (ref "P6") (pin "6") (pinfunction "6_6") (pintype "passive+no_connect"))
    )
    (net (code "127") (name "unconnected-(P8-Pad5)") (class "Default")
      (node (ref "P8") (pin "5") (pinfunction "5_5") (pintype "passive+no_connect"))
    )
    (net (code "128") (name "unconnected-(P8-Pad6)") (class "Default")
      (node (ref "P8") (pin "6") (pinfunction "6_6") (pintype "passive+no_connect"))
    )
    (net (code "129") (name "unconnected-(RN3-Pad1)") (class "Default")
      (node (ref "RN3") (pin "1") (pinfunction "1_1") (pintype "passive+no_connect"))
    )
    (net (code "130") (name "unconnected-(RN3-Pad8)") (class "Default")
      (node (ref "RN3") (pin "8") (pinfunction "8_8") (pintype "passive+no_connect"))
    )
    (net (code "131") (name "unconnected-(RN4-Pad1)") (class "Default")
      (node (ref "RN4") (pin "1") (pinfunction "1_1") (pintype "passive+no_connect"))
    )
    (net (code "132") (name "unconnected-(RN4-Pad8)") (class "Default")
      (node (ref "RN4") (pin "8") (pinfunction "8_8") (pintype "passive+no_connect"))
    )
    (net (code "133") (name "unconnected-(RN5-Pad1)") (class "Default")
      (node (ref "RN5") (pin "1") (pinfunction "1_1") (pintype "passive+no_connect"))
    )
    (net (code "134") (name "unconnected-(RN5-Pad8)") (class "Default")
      (node (ref "RN5") (pin "8") (pinfunction "8_8") (pintype "passive+no_connect"))
    )
    (net (code "135") (name "unconnected-(RN6-Pad1)") (class "Default")
      (node (ref "RN6") (pin "1") (pinfunction "1_1") (pintype "passive+no_connect"))
    )
    (net (code "136") (name "unconnected-(RN6-Pad8)") (class "Default")
      (node (ref "RN6") (pin "8") (pinfunction "8_8") (pintype "passive+no_connect"))
    )
    (net (code "137") (name "unconnected-(U2-EN-Pad7)") (class "Default")
      (node (ref "U2") (pin "7") (pinfunction "EN_7") (pintype "passive+no_connect"))
    )
    (net (code "138") (name "unconnected-(U5-2A-Pad3)") (class "Default")
      (node (ref "U5") (pin "3") (pinfunction "2A_3") (pintype "passive+no_connect"))
    )
    (net (code "139") (name "unconnected-(U5-2Y-Pad4)") (class "Default")
      (node (ref "U5") (pin "4") (pinfunction "2Y_4") (pintype "passive+no_connect"))
    )
    (net (code "140") (name "unconnected-(USB1-ID-Pad4)") (class "Default")
      (node (ref "USB1") (pin "4") (pinfunction "ID_4") (pintype "passive+no_connect"))
    )
    (net (code "141") (name "unconnected-(USB1-VBUS-Pad1)") (class "Default")
      (node (ref "USB1") (pin "1") (pinfunction "VBUS_1") (pintype "passive+no_connect"))
    )
  )
)
